# Replicape_A4A.net
KiCad netlist of a schematic drawn in EAGLE
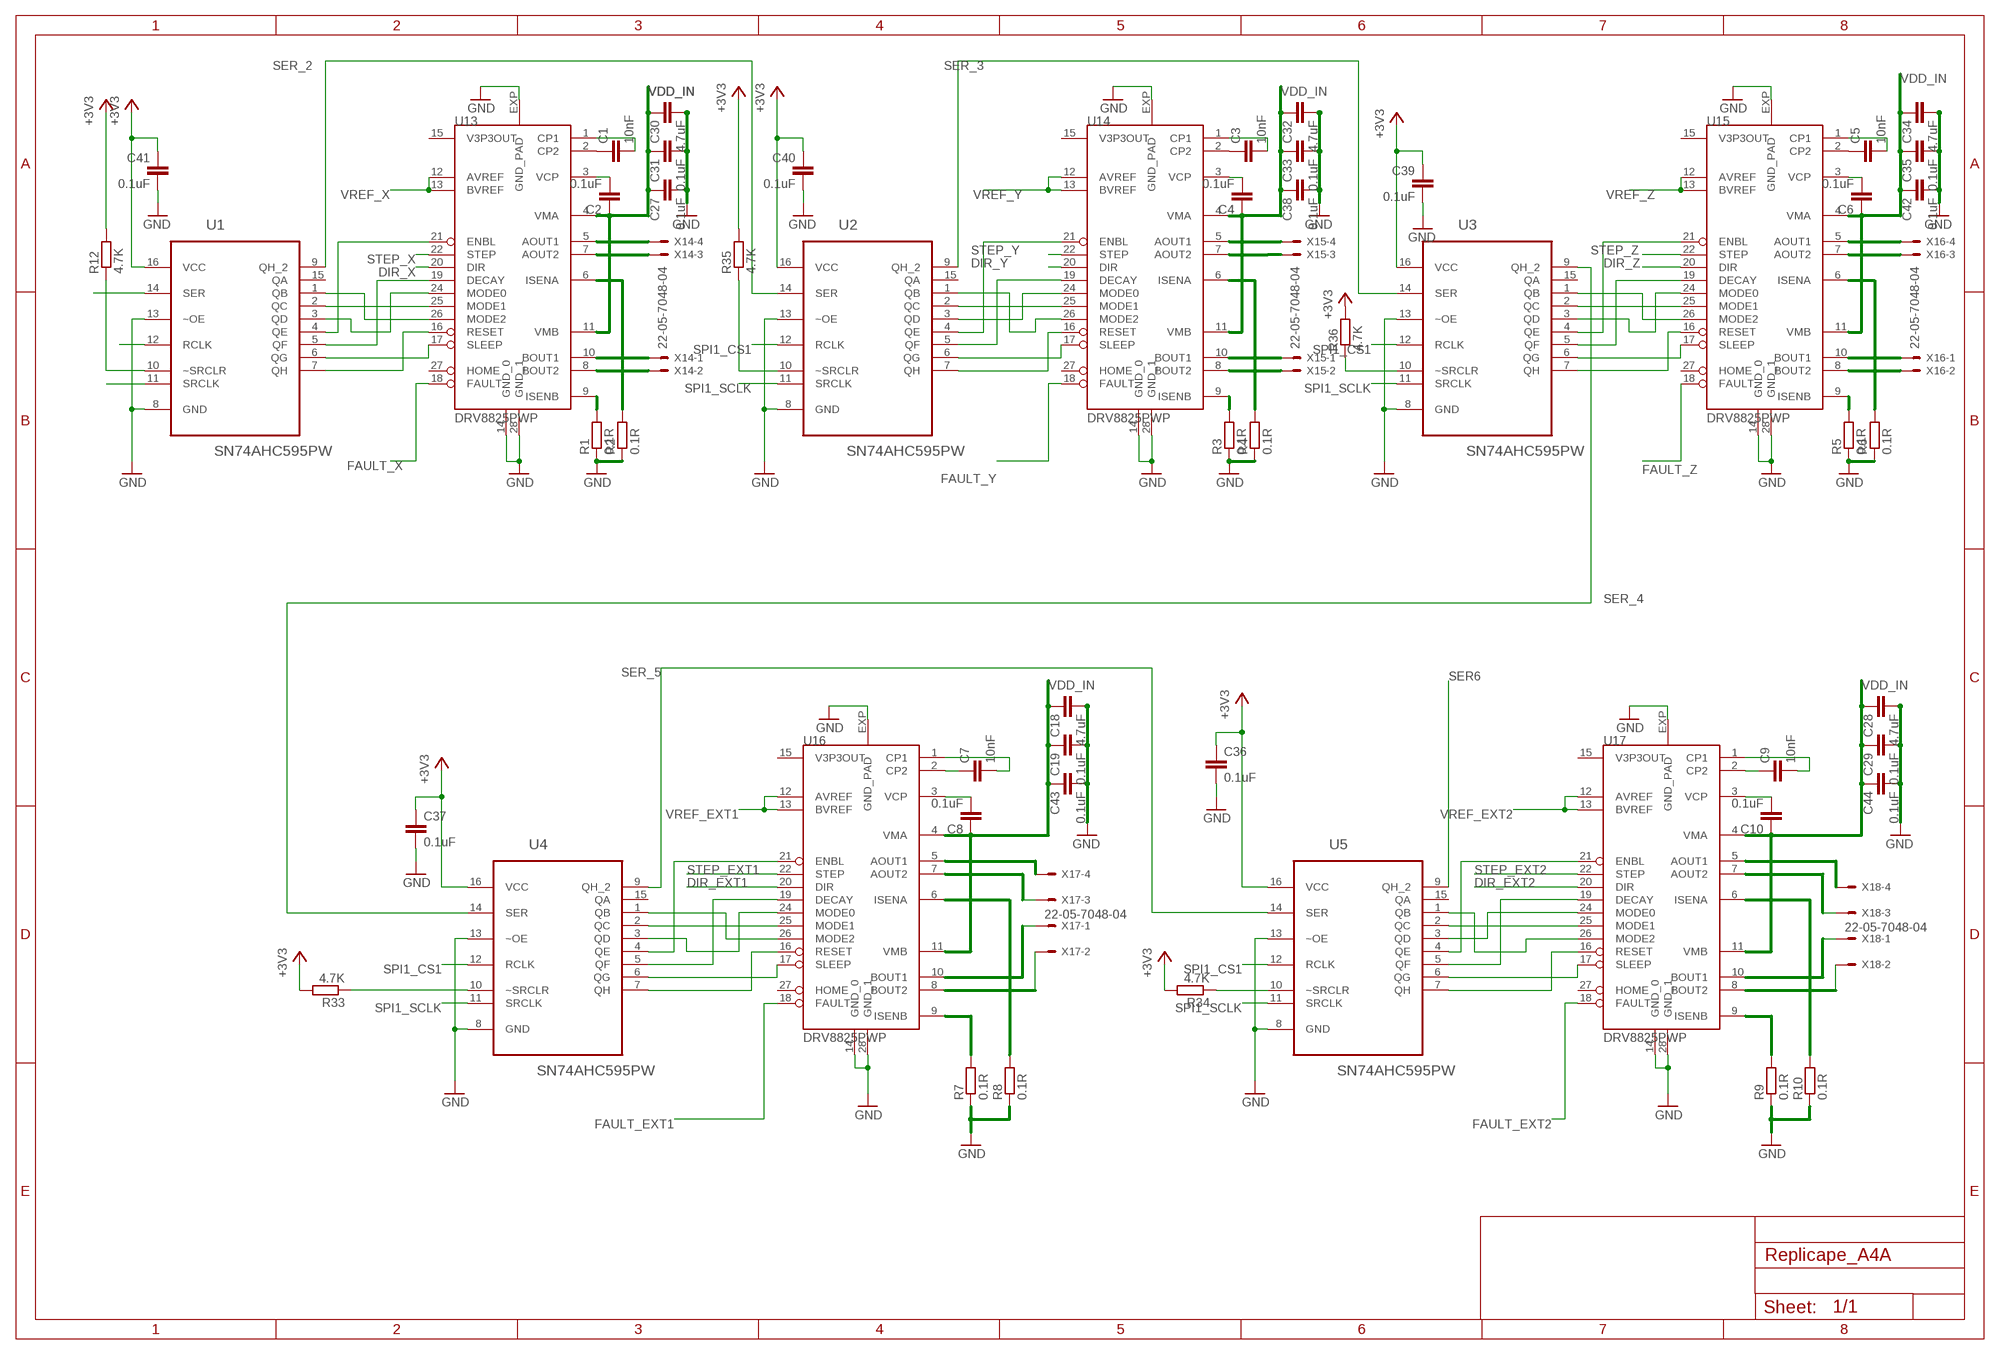
[diagram p0: schematic, sheet 1, part 1 of 3]
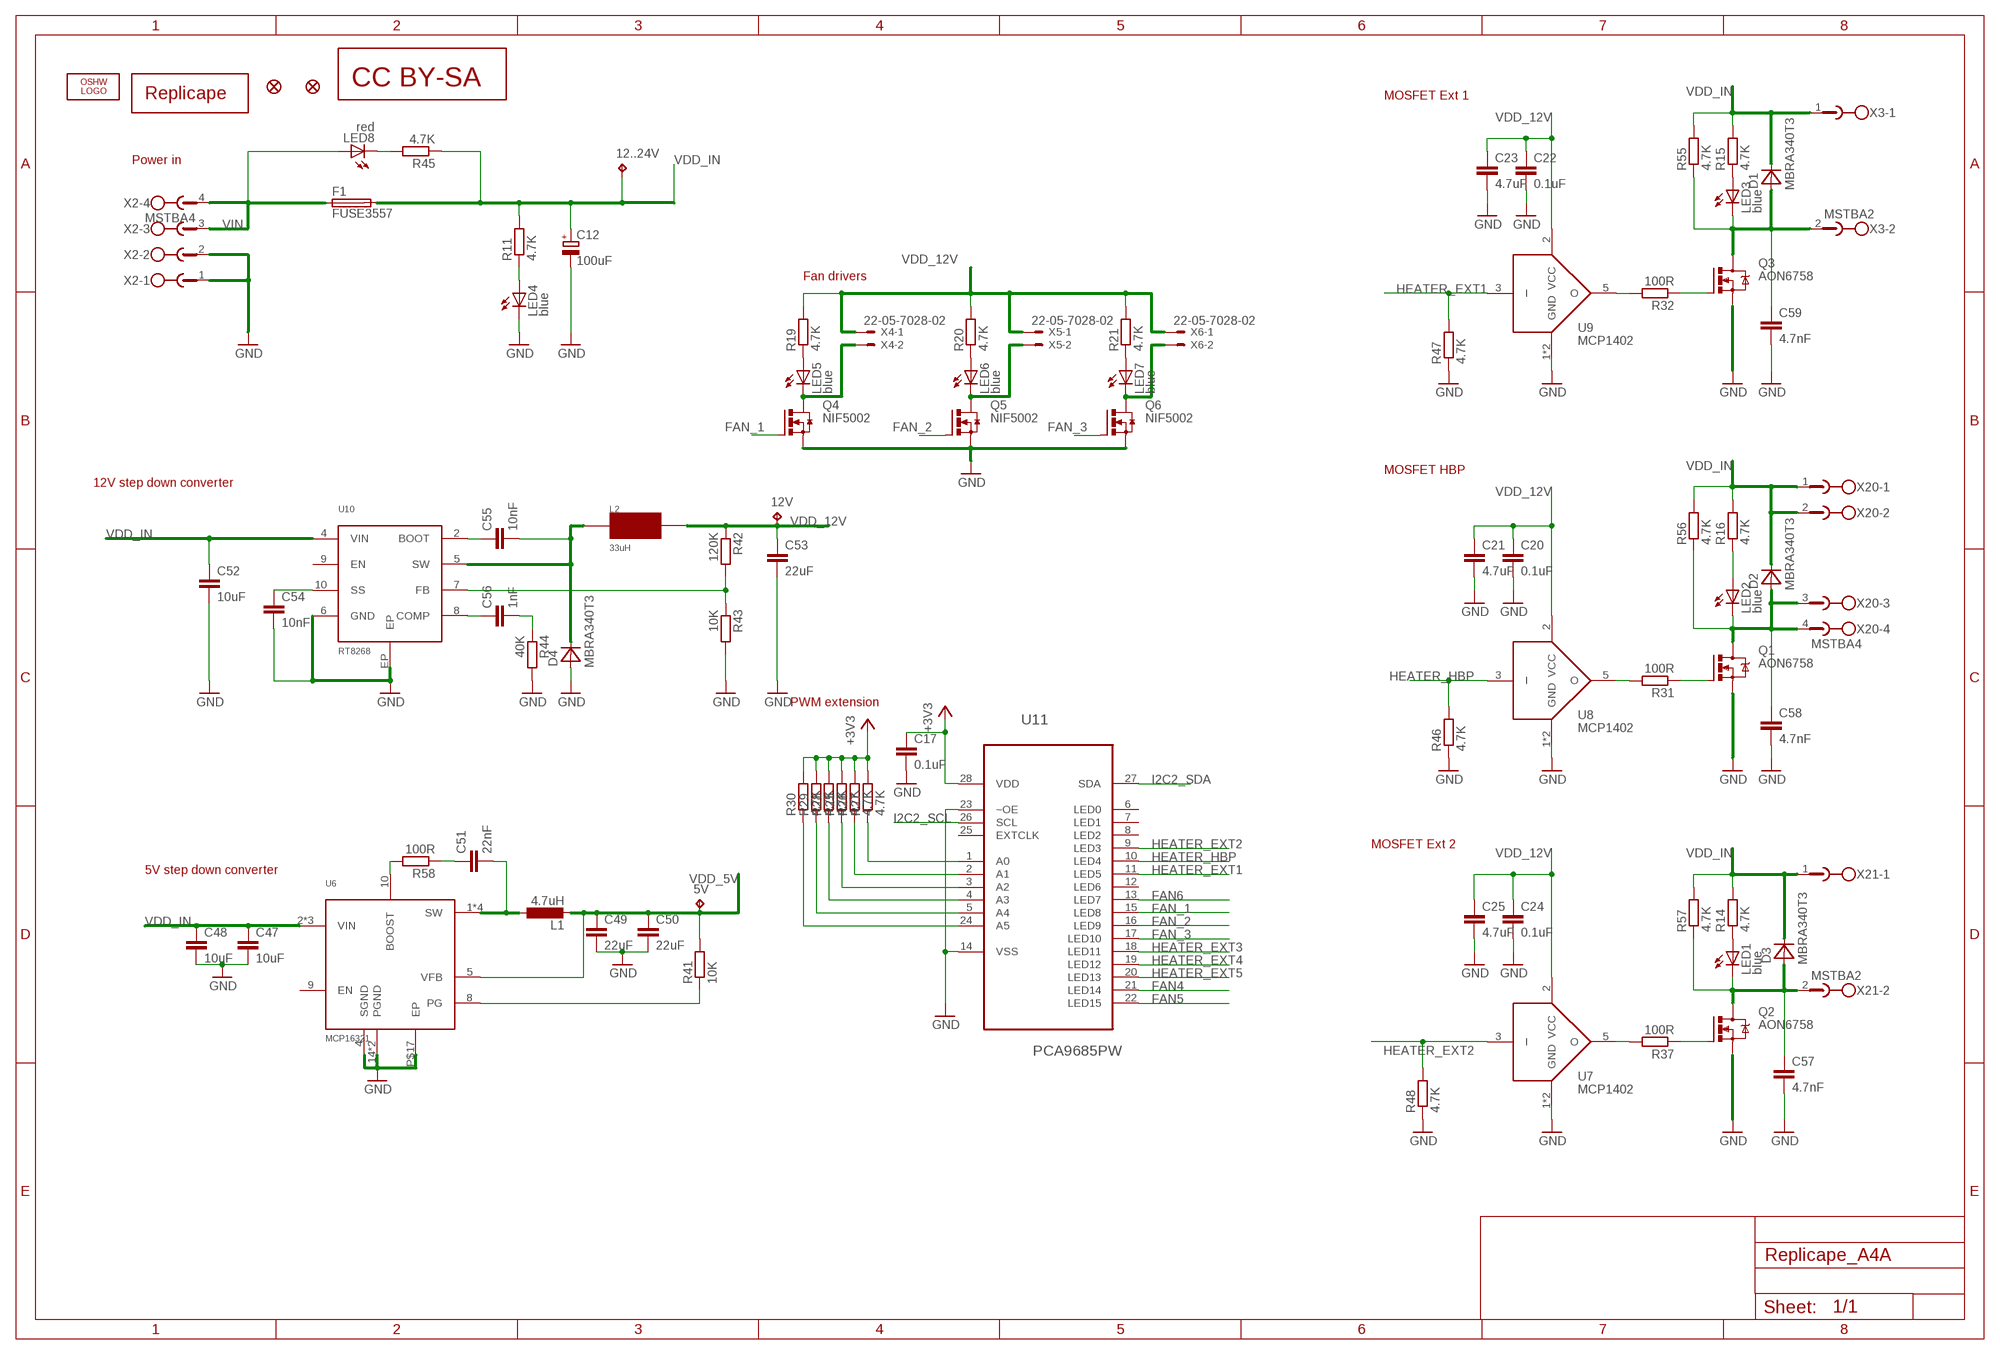
[diagram p1: schematic, sheet 1, part 2 of 3]
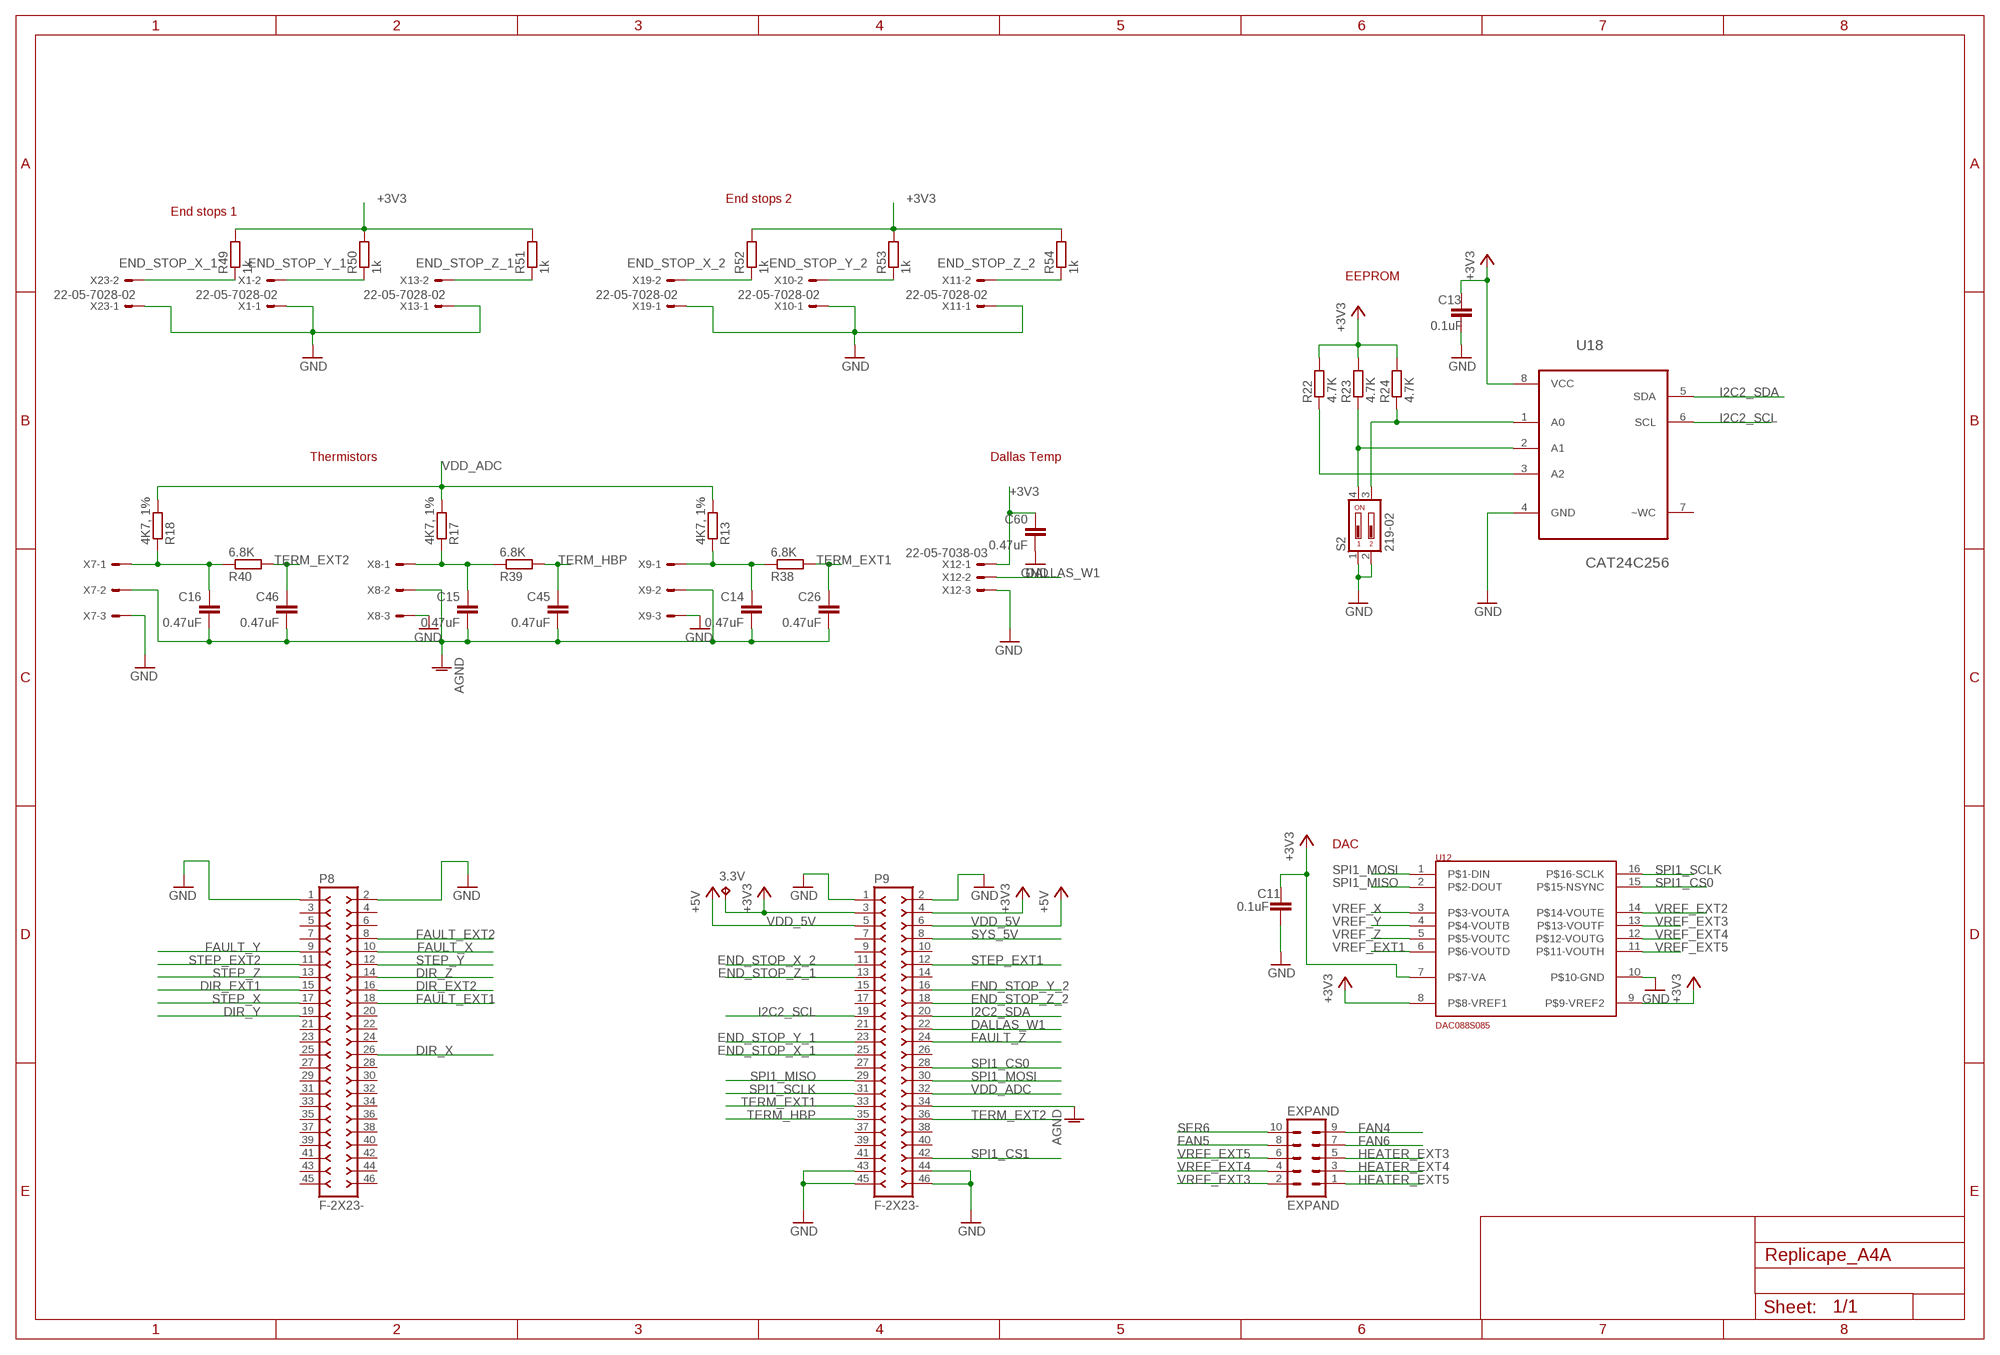
[diagram p2: schematic, sheet 1, part 3 of 3]

(export (version "E")
  (design (tool "Eeschema 10.0.6"))
  (components
    (comp (ref "3.3V")
      (value "TPB1,27")
      (footprint "eagle-import:B1,27")
      (libsource (lib "eagle-import") (part "TPB1,27"))
    )
    (comp (ref "5V")
      (value "TPB1,27")
      (footprint "eagle-import:B1,27")
      (libsource (lib "eagle-import") (part "TPB1,27"))
    )
    (comp (ref "12..24V")
      (value "TPB1,27")
      (footprint "eagle-import:B1,27")
      (libsource (lib "eagle-import") (part "TPB1,27"))
    )
    (comp (ref "12V")
      (value "TPB1,27")
      (footprint "eagle-import:B1,27")
      (libsource (lib "eagle-import") (part "TPB1,27"))
    )
    (comp (ref "C1")
      (value "10nF")
      (footprint "eagle-import:C0402")
      (libsource (lib "eagle-import") (part "C-EUC0402"))
    )
    (comp (ref "C2")
      (value "0.1uF")
      (footprint "eagle-import:C0402")
      (libsource (lib "eagle-import") (part "C-EUC0402"))
    )
    (comp (ref "C3")
      (value "10nF")
      (footprint "eagle-import:C0402")
      (libsource (lib "eagle-import") (part "C-EUC0402"))
    )
    (comp (ref "C4")
      (value "0.1uF")
      (footprint "eagle-import:C0402")
      (libsource (lib "eagle-import") (part "C-EUC0402"))
    )
    (comp (ref "C5")
      (value "10nF")
      (footprint "eagle-import:C0402")
      (libsource (lib "eagle-import") (part "C-EUC0402"))
    )
    (comp (ref "C6")
      (value "0.1uF")
      (footprint "eagle-import:C0402")
      (libsource (lib "eagle-import") (part "C-EUC0402"))
    )
    (comp (ref "C7")
      (value "10nF")
      (footprint "eagle-import:C0402")
      (libsource (lib "eagle-import") (part "C-EUC0402"))
    )
    (comp (ref "C8")
      (value "0.1uF")
      (footprint "eagle-import:C0402")
      (libsource (lib "eagle-import") (part "C-EUC0402"))
    )
    (comp (ref "C9")
      (value "10nF")
      (footprint "eagle-import:C0402")
      (libsource (lib "eagle-import") (part "C-EUC0402"))
    )
    (comp (ref "C10")
      (value "0.1uF")
      (footprint "eagle-import:C0402")
      (libsource (lib "eagle-import") (part "C-EUC0402"))
    )
    (comp (ref "C11")
      (value "0.1uF")
      (footprint "eagle-import:C0402")
      (libsource (lib "eagle-import") (part "C-EUC0402"))
    )
    (comp (ref "C12")
      (value "100uF")
      (footprint "eagle-import:140CLH-0810")
      (libsource (lib "eagle-import") (part "CPOL-EU140CLH-0810"))
    )
    (comp (ref "C13")
      (value "0.1uF")
      (footprint "eagle-import:C0402")
      (libsource (lib "eagle-import") (part "C-EUC0402"))
    )
    (comp (ref "C14")
      (value "0.47uF")
      (footprint "eagle-import:C0402")
      (libsource (lib "eagle-import") (part "C-EUC0402"))
    )
    (comp (ref "C15")
      (value "0.47uF")
      (footprint "eagle-import:C0402")
      (libsource (lib "eagle-import") (part "C-EUC0402"))
    )
    (comp (ref "C16")
      (value "0.47uF")
      (footprint "eagle-import:C0402")
      (libsource (lib "eagle-import") (part "C-EUC0402"))
    )
    (comp (ref "C17")
      (value "0.1uF")
      (footprint "eagle-import:C0402")
      (libsource (lib "eagle-import") (part "C-EUC0402"))
    )
    (comp (ref "C18")
      (value "4.7uF")
      (footprint "eagle-import:C0603")
      (libsource (lib "eagle-import") (part "C-EUC0603"))
    )
    (comp (ref "C19")
      (value "0.1uF")
      (footprint "eagle-import:C0402")
      (libsource (lib "eagle-import") (part "C-EUC0402"))
    )
    (comp (ref "C20")
      (value "0.1uF")
      (footprint "eagle-import:C0402")
      (libsource (lib "eagle-import") (part "C-EUC0402"))
    )
    (comp (ref "C21")
      (value "4.7uF")
      (footprint "eagle-import:C0402")
      (libsource (lib "eagle-import") (part "C-EUC0402"))
    )
    (comp (ref "C22")
      (value "0.1uF")
      (footprint "eagle-import:C0402")
      (libsource (lib "eagle-import") (part "C-EUC0402"))
    )
    (comp (ref "C23")
      (value "4.7uF")
      (footprint "eagle-import:C0402")
      (libsource (lib "eagle-import") (part "C-EUC0402"))
    )
    (comp (ref "C24")
      (value "0.1uF")
      (footprint "eagle-import:C0402")
      (libsource (lib "eagle-import") (part "C-EUC0402"))
    )
    (comp (ref "C25")
      (value "4.7uF")
      (footprint "eagle-import:C0402")
      (libsource (lib "eagle-import") (part "C-EUC0402"))
    )
    (comp (ref "C26")
      (value "0.47uF")
      (footprint "eagle-import:C0402")
      (libsource (lib "eagle-import") (part "C-EUC0402"))
    )
    (comp (ref "C27")
      (value "0.1uF")
      (footprint "eagle-import:C0402")
      (libsource (lib "eagle-import") (part "C-EUC0402"))
    )
    (comp (ref "C28")
      (value "4.7uF")
      (footprint "eagle-import:C0603")
      (libsource (lib "eagle-import") (part "C-EUC0603"))
    )
    (comp (ref "C29")
      (value "0.1uF")
      (footprint "eagle-import:C0402")
      (libsource (lib "eagle-import") (part "C-EUC0402"))
    )
    (comp (ref "C30")
      (value "4.7uF")
      (footprint "eagle-import:C0603")
      (libsource (lib "eagle-import") (part "C-EUC0603"))
    )
    (comp (ref "C31")
      (value "0.1uF")
      (footprint "eagle-import:C0402")
      (libsource (lib "eagle-import") (part "C-EUC0402"))
    )
    (comp (ref "C32")
      (value "4.7uF")
      (footprint "eagle-import:C0603")
      (libsource (lib "eagle-import") (part "C-EUC0603"))
    )
    (comp (ref "C33")
      (value "0.1uF")
      (footprint "eagle-import:C0402")
      (libsource (lib "eagle-import") (part "C-EUC0402"))
    )
    (comp (ref "C34")
      (value "4.7uF")
      (footprint "eagle-import:C0603")
      (libsource (lib "eagle-import") (part "C-EUC0603"))
    )
    (comp (ref "C35")
      (value "0.1uF")
      (footprint "eagle-import:C0402")
      (libsource (lib "eagle-import") (part "C-EUC0402"))
    )
    (comp (ref "C36")
      (value "0.1uF")
      (footprint "eagle-import:C0402")
      (libsource (lib "eagle-import") (part "C-EUC0402"))
    )
    (comp (ref "C37")
      (value "0.1uF")
      (footprint "eagle-import:C0402")
      (libsource (lib "eagle-import") (part "C-EUC0402"))
    )
    (comp (ref "C38")
      (value "0.1uF")
      (footprint "eagle-import:C0402")
      (libsource (lib "eagle-import") (part "C-EUC0402"))
    )
    (comp (ref "C39")
      (value "0.1uF")
      (footprint "eagle-import:C0402")
      (libsource (lib "eagle-import") (part "C-EUC0402"))
    )
    (comp (ref "C40")
      (value "0.1uF")
      (footprint "eagle-import:C0402")
      (libsource (lib "eagle-import") (part "C-EUC0402"))
    )
    (comp (ref "C41")
      (value "0.1uF")
      (footprint "eagle-import:C0402")
      (libsource (lib "eagle-import") (part "C-EUC0402"))
    )
    (comp (ref "C42")
      (value "0.1uF")
      (footprint "eagle-import:C0402")
      (libsource (lib "eagle-import") (part "C-EUC0402"))
    )
    (comp (ref "C43")
      (value "0.1uF")
      (footprint "eagle-import:C0402")
      (libsource (lib "eagle-import") (part "C-EUC0402"))
    )
    (comp (ref "C44")
      (value "0.1uF")
      (footprint "eagle-import:C0402")
      (libsource (lib "eagle-import") (part "C-EUC0402"))
    )
    (comp (ref "C45")
      (value "0.47uF")
      (footprint "eagle-import:C0402")
      (libsource (lib "eagle-import") (part "C-EUC0402"))
    )
    (comp (ref "C46")
      (value "0.47uF")
      (footprint "eagle-import:C0402")
      (libsource (lib "eagle-import") (part "C-EUC0402"))
    )
    (comp (ref "C47")
      (value "10uF")
      (footprint "eagle-import:C1206")
      (libsource (lib "eagle-import") (part "C-EUC1206"))
    )
    (comp (ref "C48")
      (value "10uF")
      (footprint "eagle-import:C1206")
      (libsource (lib "eagle-import") (part "C-EUC1206"))
    )
    (comp (ref "C49")
      (value "22uF")
      (footprint "eagle-import:C0805")
      (libsource (lib "eagle-import") (part "C-EUC0805"))
    )
    (comp (ref "C50")
      (value "22uF")
      (footprint "eagle-import:C0805")
      (libsource (lib "eagle-import") (part "C-EUC0805"))
    )
    (comp (ref "C51")
      (value "22nF")
      (footprint "eagle-import:C0402")
      (libsource (lib "eagle-import") (part "C-EUC0402"))
    )
    (comp (ref "C52")
      (value "10uF")
      (footprint "eagle-import:C1206")
      (libsource (lib "eagle-import") (part "C-EUC1206"))
    )
    (comp (ref "C53")
      (value "22uF")
      (footprint "eagle-import:C0805")
      (libsource (lib "eagle-import") (part "C-EUC0805"))
    )
    (comp (ref "C54")
      (value "10nF")
      (footprint "eagle-import:C0402")
      (libsource (lib "eagle-import") (part "C-EUC0402"))
    )
    (comp (ref "C55")
      (value "10nF")
      (footprint "eagle-import:C0402")
      (libsource (lib "eagle-import") (part "C-EUC0402"))
    )
    (comp (ref "C56")
      (value "1nF")
      (footprint "eagle-import:C0402")
      (libsource (lib "eagle-import") (part "C-EUC0402"))
    )
    (comp (ref "C57")
      (value "4.7nF")
      (footprint "eagle-import:C0402")
      (libsource (lib "eagle-import") (part "C-EUC0402"))
    )
    (comp (ref "C58")
      (value "4.7nF")
      (footprint "eagle-import:C0402")
      (libsource (lib "eagle-import") (part "C-EUC0402"))
    )
    (comp (ref "C59")
      (value "4.7nF")
      (footprint "eagle-import:C0402")
      (libsource (lib "eagle-import") (part "C-EUC0402"))
    )
    (comp (ref "C60")
      (value "0.47uF")
      (footprint "eagle-import:C0402")
      (libsource (lib "eagle-import") (part "C-EUC0402"))
    )
    (comp (ref "D1")
      (value "MBRA340T3")
      (footprint "eagle-import:SMA")
      (libsource (lib "eagle-import") (part "MBRA340T3"))
    )
    (comp (ref "D2")
      (value "MBRA340T3")
      (footprint "eagle-import:SMA")
      (libsource (lib "eagle-import") (part "MBRA340T3"))
    )
    (comp (ref "D3")
      (value "MBRA340T3")
      (footprint "eagle-import:SMA")
      (libsource (lib "eagle-import") (part "MBRA340T3"))
    )
    (comp (ref "D4")
      (value "MBRA340T3")
      (footprint "eagle-import:SMA")
      (libsource (lib "eagle-import") (part "MBRA340T3"))
    )
    (comp (ref "EXPAND")
      (value "EXPAND")
      (footprint "eagle-import:MA05-2")
      (libsource (lib "eagle-import") (part "MA05-2"))
    )
    (comp (ref "F1")
      (value "FUSE3557")
      (footprint "eagle-import:3557")
      (libsource (lib "eagle-import") (part "FUSE3557"))
    )
    (comp (ref "JP1")
      (value "FIDUCIAL1X2.5")
      (footprint "eagle-import:FIDUCIAL-1X2.5")
      (libsource (lib "eagle-import") (part "FIDUCIAL1X2.5"))
    )
    (comp (ref "JP2")
      (value "FIDUCIAL1X2.5")
      (footprint "eagle-import:FIDUCIAL-1X2.5")
      (libsource (lib "eagle-import") (part "FIDUCIAL1X2.5"))
    )
    (comp (ref "L1")
      (value "4.7uH")
      (footprint "eagle-import:VLC5020")
      (libsource (lib "eagle-import") (part "L-EUVLC"))
    )
    (comp (ref "L2")
      (value "33uH")
      (footprint "eagle-import:NR8040T330")
      (libsource (lib "eagle-import") (part "RT8040T330"))
    )
    (comp (ref "LED1")
      (value "blue")
      (footprint "eagle-import:CHIP-LED0603")
      (libsource (lib "eagle-import") (part "LEDCHIP-LED0603"))
    )
    (comp (ref "LED2")
      (value "blue")
      (footprint "eagle-import:CHIP-LED0603")
      (libsource (lib "eagle-import") (part "LEDCHIP-LED0603"))
    )
    (comp (ref "LED3")
      (value "blue")
      (footprint "eagle-import:CHIP-LED0603")
      (libsource (lib "eagle-import") (part "LEDCHIP-LED0603"))
    )
    (comp (ref "LED4")
      (value "blue")
      (footprint "eagle-import:CHIP-LED0603")
      (libsource (lib "eagle-import") (part "LEDCHIP-LED0603"))
    )
    (comp (ref "LED5")
      (value "blue")
      (footprint "eagle-import:CHIP-LED0603")
      (libsource (lib "eagle-import") (part "LEDCHIP-LED0603"))
    )
    (comp (ref "LED6")
      (value "blue")
      (footprint "eagle-import:CHIP-LED0603")
      (libsource (lib "eagle-import") (part "LEDCHIP-LED0603"))
    )
    (comp (ref "LED7")
      (value "blue")
      (footprint "eagle-import:CHIP-LED0603")
      (libsource (lib "eagle-import") (part "LEDCHIP-LED0603"))
    )
    (comp (ref "LED8")
      (value "red")
      (footprint "eagle-import:CHIP-LED0603")
      (libsource (lib "eagle-import") (part "LEDCHIP-LED0603"))
    )
    (comp (ref "LOGO1")
      (value "OSHW_LOGO_FILLX0200-NT")
      (footprint "eagle-import:OSHW_FILLX200_NOTEXT")
      (libsource (lib "eagle-import") (part "OSHW_LOGO_FILLX0200-NT"))
    )
    (comp (ref "P8")
      (value "F-2X23-")
      (footprint "eagle-import:DIL-100-2X23")
      (libsource (lib "eagle-import") (part "F-2X23-"))
    )
    (comp (ref "P9")
      (value "F-2X23-")
      (footprint "eagle-import:DIL-100-2X23")
      (libsource (lib "eagle-import") (part "F-2X23-"))
    )
    (comp (ref "Q1")
      (value "AON6758")
      (footprint "eagle-import:8-DFN-EP-(5X6)")
      (libsource (lib "eagle-import") (part "AON6758"))
    )
    (comp (ref "Q2")
      (value "AON6758")
      (footprint "eagle-import:8-DFN-EP-(5X6)")
      (libsource (lib "eagle-import") (part "AON6758"))
    )
    (comp (ref "Q3")
      (value "AON6758")
      (footprint "eagle-import:8-DFN-EP-(5X6)")
      (libsource (lib "eagle-import") (part "AON6758"))
    )
    (comp (ref "Q4")
      (value "NIF5002")
      (footprint "eagle-import:SOT223")
      (libsource (lib "eagle-import") (part "N-HEXFET-2D_?-SOT232"))
    )
    (comp (ref "Q5")
      (value "NIF5002")
      (footprint "eagle-import:SOT223")
      (libsource (lib "eagle-import") (part "N-HEXFET-2D_?-SOT232"))
    )
    (comp (ref "Q6")
      (value "NIF5002")
      (footprint "eagle-import:SOT223")
      (libsource (lib "eagle-import") (part "N-HEXFET-2D_?-SOT232"))
    )
    (comp (ref "R1")
      (value "0.1R")
      (footprint "eagle-import:R0805")
      (libsource (lib "eagle-import") (part "R-EU_R0805"))
    )
    (comp (ref "R2")
      (value "0.1R")
      (footprint "eagle-import:R0805")
      (libsource (lib "eagle-import") (part "R-EU_R0805"))
    )
    (comp (ref "R3")
      (value "0.1R")
      (footprint "eagle-import:R0805")
      (libsource (lib "eagle-import") (part "R-EU_R0805"))
    )
    (comp (ref "R4")
      (value "0.1R")
      (footprint "eagle-import:R0805")
      (libsource (lib "eagle-import") (part "R-EU_R0805"))
    )
    (comp (ref "R5")
      (value "0.1R")
      (footprint "eagle-import:R0805")
      (libsource (lib "eagle-import") (part "R-EU_R0805"))
    )
    (comp (ref "R6")
      (value "0.1R")
      (footprint "eagle-import:R0805")
      (libsource (lib "eagle-import") (part "R-EU_R0805"))
    )
    (comp (ref "R7")
      (value "0.1R")
      (footprint "eagle-import:R0805")
      (libsource (lib "eagle-import") (part "R-EU_R0805"))
    )
    (comp (ref "R8")
      (value "0.1R")
      (footprint "eagle-import:R0805")
      (libsource (lib "eagle-import") (part "R-EU_R0805"))
    )
    (comp (ref "R9")
      (value "0.1R")
      (footprint "eagle-import:R0805")
      (libsource (lib "eagle-import") (part "R-EU_R0805"))
    )
    (comp (ref "R10")
      (value "0.1R")
      (footprint "eagle-import:R0805")
      (libsource (lib "eagle-import") (part "R-EU_R0805"))
    )
    (comp (ref "R11")
      (value "4.7K")
      (footprint "eagle-import:R0402")
      (libsource (lib "eagle-import") (part "R-EU_R0402"))
    )
    (comp (ref "R12")
      (value "4.7K")
      (footprint "eagle-import:R0402")
      (libsource (lib "eagle-import") (part "R-EU_R0402"))
    )
    (comp (ref "R13")
      (value "4K7, 1%")
      (footprint "eagle-import:R0402")
      (libsource (lib "eagle-import") (part "R-EU_R0402"))
    )
    (comp (ref "R14")
      (value "4.7K")
      (footprint "eagle-import:R0402")
      (libsource (lib "eagle-import") (part "R-EU_R0402"))
    )
    (comp (ref "R15")
      (value "4.7K")
      (footprint "eagle-import:R0402")
      (libsource (lib "eagle-import") (part "R-EU_R0402"))
    )
    (comp (ref "R16")
      (value "4.7K")
      (footprint "eagle-import:R0402")
      (libsource (lib "eagle-import") (part "R-EU_R0402"))
    )
    (comp (ref "R17")
      (value "4K7, 1%")
      (footprint "eagle-import:R0402")
      (libsource (lib "eagle-import") (part "R-EU_R0402"))
    )
    (comp (ref "R18")
      (value "4K7, 1%")
      (footprint "eagle-import:R0402")
      (libsource (lib "eagle-import") (part "R-EU_R0402"))
    )
    (comp (ref "R19")
      (value "4.7K")
      (footprint "eagle-import:R0402")
      (libsource (lib "eagle-import") (part "R-EU_R0402"))
    )
    (comp (ref "R20")
      (value "4.7K")
      (footprint "eagle-import:R0402")
      (libsource (lib "eagle-import") (part "R-EU_R0402"))
    )
    (comp (ref "R21")
      (value "4.7K")
      (footprint "eagle-import:R0402")
      (libsource (lib "eagle-import") (part "R-EU_R0402"))
    )
    (comp (ref "R22")
      (value "4.7K")
      (footprint "eagle-import:R0402")
      (libsource (lib "eagle-import") (part "R-EU_R0402"))
    )
    (comp (ref "R23")
      (value "4.7K")
      (footprint "eagle-import:R0402")
      (libsource (lib "eagle-import") (part "R-EU_R0402"))
    )
    (comp (ref "R24")
      (value "4.7K")
      (footprint "eagle-import:R0402")
      (libsource (lib "eagle-import") (part "R-EU_R0402"))
    )
    (comp (ref "R25")
      (value "4.7K")
      (footprint "eagle-import:R0402")
      (libsource (lib "eagle-import") (part "R-EU_R0402"))
    )
    (comp (ref "R26")
      (value "4.7K")
      (footprint "eagle-import:R0402")
      (libsource (lib "eagle-import") (part "R-EU_R0402"))
    )
    (comp (ref "R27")
      (value "4.7K")
      (footprint "eagle-import:R0402")
      (libsource (lib "eagle-import") (part "R-EU_R0402"))
    )
    (comp (ref "R28")
      (value "4.7K")
      (footprint "eagle-import:R0402")
      (libsource (lib "eagle-import") (part "R-EU_R0402"))
    )
    (comp (ref "R29")
      (value "4.7K")
      (footprint "eagle-import:R0402")
      (libsource (lib "eagle-import") (part "R-EU_R0402"))
    )
    (comp (ref "R30")
      (value "4.7K")
      (footprint "eagle-import:R0402")
      (libsource (lib "eagle-import") (part "R-EU_R0402"))
    )
    (comp (ref "R31")
      (value "100R")
      (footprint "eagle-import:R0402")
      (libsource (lib "eagle-import") (part "R-EU_R0402"))
    )
    (comp (ref "R32")
      (value "100R")
      (footprint "eagle-import:R0402")
      (libsource (lib "eagle-import") (part "R-EU_R0402"))
    )
    (comp (ref "R33")
      (value "4.7K")
      (footprint "eagle-import:R0402")
      (libsource (lib "eagle-import") (part "R-EU_R0402"))
    )
    (comp (ref "R34")
      (value "4.7K")
      (footprint "eagle-import:R0402")
      (libsource (lib "eagle-import") (part "R-EU_R0402"))
    )
    (comp (ref "R35")
      (value "4.7K")
      (footprint "eagle-import:R0402")
      (libsource (lib "eagle-import") (part "R-EU_R0402"))
    )
    (comp (ref "R36")
      (value "4.7K")
      (footprint "eagle-import:R0402")
      (libsource (lib "eagle-import") (part "R-EU_R0402"))
    )
    (comp (ref "R37")
      (value "100R")
      (footprint "eagle-import:R0402")
      (libsource (lib "eagle-import") (part "R-EU_R0402"))
    )
    (comp (ref "R38")
      (value "6.8K")
      (footprint "eagle-import:R0402")
      (libsource (lib "eagle-import") (part "R-EU_R0402"))
    )
    (comp (ref "R39")
      (value "6.8K")
      (footprint "eagle-import:R0402")
      (libsource (lib "eagle-import") (part "R-EU_R0402"))
    )
    (comp (ref "R40")
      (value "6.8K")
      (footprint "eagle-import:R0402")
      (libsource (lib "eagle-import") (part "R-EU_R0402"))
    )
    (comp (ref "R41")
      (value "10K")
      (footprint "eagle-import:R0402")
      (libsource (lib "eagle-import") (part "R-EU_R0402"))
    )
    (comp (ref "R42")
      (value "120K")
      (footprint "eagle-import:R0402")
      (libsource (lib "eagle-import") (part "R-EU_R0402"))
    )
    (comp (ref "R43")
      (value "10K")
      (footprint "eagle-import:R0402")
      (libsource (lib "eagle-import") (part "R-EU_R0402"))
    )
    (comp (ref "R44")
      (value "40K")
      (footprint "eagle-import:R0402")
      (libsource (lib "eagle-import") (part "R-EU_R0402"))
    )
    (comp (ref "R45")
      (value "4.7K")
      (footprint "eagle-import:R0402")
      (libsource (lib "eagle-import") (part "R-EU_R0402"))
    )
    (comp (ref "R46")
      (value "4.7K")
      (footprint "eagle-import:R0402")
      (libsource (lib "eagle-import") (part "R-EU_R0402"))
    )
    (comp (ref "R47")
      (value "4.7K")
      (footprint "eagle-import:R0402")
      (libsource (lib "eagle-import") (part "R-EU_R0402"))
    )
    (comp (ref "R48")
      (value "4.7K")
      (footprint "eagle-import:R0402")
      (libsource (lib "eagle-import") (part "R-EU_R0402"))
    )
    (comp (ref "R49")
      (value "1k")
      (footprint "eagle-import:R0402")
      (libsource (lib "eagle-import") (part "R-EUR0402"))
    )
    (comp (ref "R50")
      (value "1k")
      (footprint "eagle-import:R0402")
      (libsource (lib "eagle-import") (part "R-EUR0402"))
    )
    (comp (ref "R51")
      (value "1k")
      (footprint "eagle-import:R0402")
      (libsource (lib "eagle-import") (part "R-EUR0402"))
    )
    (comp (ref "R52")
      (value "1k")
      (footprint "eagle-import:R0402")
      (libsource (lib "eagle-import") (part "R-EUR0402"))
    )
    (comp (ref "R53")
      (value "1k")
      (footprint "eagle-import:R0402")
      (libsource (lib "eagle-import") (part "R-EUR0402"))
    )
    (comp (ref "R54")
      (value "1k")
      (footprint "eagle-import:R0402")
      (libsource (lib "eagle-import") (part "R-EUR0402"))
    )
    (comp (ref "R55")
      (value "4.7K")
      (footprint "eagle-import:R0402")
      (libsource (lib "eagle-import") (part "R-EU_R0402"))
    )
    (comp (ref "R56")
      (value "4.7K")
      (footprint "eagle-import:R0402")
      (libsource (lib "eagle-import") (part "R-EU_R0402"))
    )
    (comp (ref "R57")
      (value "4.7K")
      (footprint "eagle-import:R0402")
      (libsource (lib "eagle-import") (part "R-EU_R0402"))
    )
    (comp (ref "R58")
      (value "100R")
      (footprint "eagle-import:R0402")
      (libsource (lib "eagle-import") (part "R-EU_R0402"))
    )
    (comp (ref "S2")
      (value "219-02")
      (footprint "eagle-import:CTS-219-02")
      (libsource (lib "eagle-import") (part "219-02"))
    )
    (comp (ref "U$2")
      (value "REPLICAPE-LOGO")
      (footprint "eagle-import:REPLICAPE-LOGO")
      (libsource (lib "eagle-import") (part "REPLICAPE-LOGO"))
    )
    (comp (ref "U$3")
      (value "CC-BY-SA")
      (footprint "eagle-import:CC-BY-SA")
      (libsource (lib "eagle-import") (part "CC-BY-SA"))
    )
    (comp (ref "U1")
      (value "SN74AHC595PW")
      (footprint "eagle-import:SOP65P640X120-16N")
      (libsource (lib "eagle-import") (part "SN74AHC595PW"))
    )
    (comp (ref "U2")
      (value "SN74AHC595PW")
      (footprint "eagle-import:SOP65P640X120-16N")
      (libsource (lib "eagle-import") (part "SN74AHC595PW"))
    )
    (comp (ref "U3")
      (value "SN74AHC595PW")
      (footprint "eagle-import:SOP65P640X120-16N")
      (libsource (lib "eagle-import") (part "SN74AHC595PW"))
    )
    (comp (ref "U4")
      (value "SN74AHC595PW")
      (footprint "eagle-import:SOP65P640X120-16N")
      (libsource (lib "eagle-import") (part "SN74AHC595PW"))
    )
    (comp (ref "U5")
      (value "SN74AHC595PW")
      (footprint "eagle-import:SOP65P640X120-16N")
      (libsource (lib "eagle-import") (part "SN74AHC595PW"))
    )
    (comp (ref "U6")
      (value "MCP16321")
      (footprint "eagle-import:QFN-16")
      (libsource (lib "eagle-import") (part "MCP16321"))
    )
    (comp (ref "U7")
      (value "MCP1402")
      (footprint "eagle-import:SOT23-5L")
      (libsource (lib "eagle-import") (part "MCP1402"))
    )
    (comp (ref "U8")
      (value "MCP1402")
      (footprint "eagle-import:SOT23-5L")
      (libsource (lib "eagle-import") (part "MCP1402"))
    )
    (comp (ref "U9")
      (value "MCP1402")
      (footprint "eagle-import:SOT23-5L")
      (libsource (lib "eagle-import") (part "MCP1402"))
    )
    (comp (ref "U10")
      (value "RT8268")
      (footprint "eagle-import:MSOP10")
      (libsource (lib "eagle-import") (part "RT8268"))
    )
    (comp (ref "U11")
      (value "PCA9685PW")
      (footprint "eagle-import:SOP65P640X110-28N")
      (libsource (lib "eagle-import") (part "PCA9685PW"))
    )
    (comp (ref "U12")
      (value "DAC088S085")
      (footprint "eagle-import:TSSOP-16")
      (libsource (lib "eagle-import") (part "DAC088S085"))
    )
    (comp (ref "U13")
      (value "DRV8825PWP")
      (footprint "eagle-import:TSSOP-28")
      (libsource (lib "eagle-import") (part "DRV8825PWP"))
    )
    (comp (ref "U14")
      (value "DRV8825PWP")
      (footprint "eagle-import:TSSOP-28")
      (libsource (lib "eagle-import") (part "DRV8825PWP"))
    )
    (comp (ref "U15")
      (value "DRV8825PWP")
      (footprint "eagle-import:TSSOP-28")
      (libsource (lib "eagle-import") (part "DRV8825PWP"))
    )
    (comp (ref "U16")
      (value "DRV8825PWP")
      (footprint "eagle-import:TSSOP-28")
      (libsource (lib "eagle-import") (part "DRV8825PWP"))
    )
    (comp (ref "U17")
      (value "DRV8825PWP")
      (footprint "eagle-import:TSSOP-28")
      (libsource (lib "eagle-import") (part "DRV8825PWP"))
    )
    (comp (ref "U18")
      (value "CAT24C256")
      (footprint "eagle-import:SOIC127P600X175-8N")
      (libsource (lib "eagle-import") (part "CAT24C256"))
    )
    (comp (ref "X1")
      (value "22-05-7028-02")
      (footprint "eagle-import:7395-02")
      (libsource (lib "eagle-import") (part "22-?-0205-7028"))
    )
    (comp (ref "X2")
      (value "MSTBA4")
      (footprint "eagle-import:MSTBA4")
      (libsource (lib "eagle-import") (part "MSTBA4"))
    )
    (comp (ref "X3")
      (value "MSTBA2")
      (footprint "eagle-import:MSTBA2")
      (libsource (lib "eagle-import") (part "MSTBA2"))
    )
    (comp (ref "X4")
      (value "22-05-7028-02")
      (footprint "eagle-import:7395-02")
      (libsource (lib "eagle-import") (part "22-?-0205-7028"))
    )
    (comp (ref "X5")
      (value "22-05-7028-02")
      (footprint "eagle-import:7395-02")
      (libsource (lib "eagle-import") (part "22-?-0205-7028"))
    )
    (comp (ref "X6")
      (value "22-05-7028-02")
      (footprint "eagle-import:7395-02")
      (libsource (lib "eagle-import") (part "22-?-0205-7028"))
    )
    (comp (ref "X7")
      (value "22-05-7038-03")
      (footprint "eagle-import:7395-03")
      (libsource (lib "eagle-import") (part "22-?-0305-7038"))
    )
    (comp (ref "X8")
      (value "22-05-7038-03")
      (footprint "eagle-import:7395-03")
      (libsource (lib "eagle-import") (part "22-?-0305-7038"))
    )
    (comp (ref "X9")
      (value "22-05-7038-03")
      (footprint "eagle-import:7395-03")
      (libsource (lib "eagle-import") (part "22-?-0305-7038"))
    )
    (comp (ref "X10")
      (value "22-05-7028-02")
      (footprint "eagle-import:7395-02")
      (libsource (lib "eagle-import") (part "22-?-0205-7028"))
    )
    (comp (ref "X11")
      (value "22-05-7028-02")
      (footprint "eagle-import:7395-02")
      (libsource (lib "eagle-import") (part "22-?-0205-7028"))
    )
    (comp (ref "X12")
      (value "22-05-7038-03")
      (footprint "eagle-import:7395-03")
      (libsource (lib "eagle-import") (part "22-?-0305-7038"))
    )
    (comp (ref "X13")
      (value "22-05-7028-02")
      (footprint "eagle-import:7395-02")
      (libsource (lib "eagle-import") (part "22-?-0205-7028"))
    )
    (comp (ref "X14")
      (value "22-05-7048-04")
      (footprint "eagle-import:7395-04")
      (libsource (lib "eagle-import") (part "22-?-0405-7048"))
    )
    (comp (ref "X15")
      (value "22-05-7048-04")
      (footprint "eagle-import:7395-04")
      (libsource (lib "eagle-import") (part "22-?-0405-7048"))
    )
    (comp (ref "X16")
      (value "22-05-7048-04")
      (footprint "eagle-import:7395-04")
      (libsource (lib "eagle-import") (part "22-?-0405-7048"))
    )
    (comp (ref "X17")
      (value "22-05-7048-04")
      (footprint "eagle-import:7395-04")
      (libsource (lib "eagle-import") (part "22-?-0405-7048"))
    )
    (comp (ref "X18")
      (value "22-05-7048-04")
      (footprint "eagle-import:7395-04")
      (libsource (lib "eagle-import") (part "22-?-0405-7048"))
    )
    (comp (ref "X19")
      (value "22-05-7028-02")
      (footprint "eagle-import:7395-02")
      (libsource (lib "eagle-import") (part "22-?-0205-7028"))
    )
    (comp (ref "X20")
      (value "MSTBA4")
      (footprint "eagle-import:MSTBA4")
      (libsource (lib "eagle-import") (part "MSTBA4"))
    )
    (comp (ref "X21")
      (value "MSTBA2")
      (footprint "eagle-import:MSTBA2")
      (libsource (lib "eagle-import") (part "MSTBA2"))
    )
    (comp (ref "X23")
      (value "22-05-7028-02")
      (footprint "eagle-import:7395-02")
      (libsource (lib "eagle-import") (part "22-?-0205-7028"))
    )
  )
  (nets
    (net (code "1") (name "+3V3") (class "Default")
      (node (ref "3.3V") (pin "TP") (pinfunction "TP_TP") (pintype "input"))
      (node (ref "C11") (pin "1") (pinfunction "1_1") (pintype "passive"))
      (node (ref "C13") (pin "1") (pinfunction "1_1") (pintype "passive"))
      (node (ref "C17") (pin "1") (pinfunction "1_1") (pintype "passive"))
      (node (ref "C36") (pin "1") (pinfunction "1_1") (pintype "passive"))
      (node (ref "C37") (pin "1") (pinfunction "1_1") (pintype "passive"))
      (node (ref "C39") (pin "1") (pinfunction "1_1") (pintype "passive"))
      (node (ref "C40") (pin "1") (pinfunction "1_1") (pintype "passive"))
      (node (ref "C41") (pin "1") (pinfunction "1_1") (pintype "passive"))
      (node (ref "C60") (pin "1") (pinfunction "1_1") (pintype "passive"))
      (node (ref "P9") (pin "3") (pinfunction "3_3") (pintype "passive"))
      (node (ref "P9") (pin "4") (pinfunction "4_4") (pintype "passive"))
      (node (ref "R12") (pin "2") (pinfunction "2_2") (pintype "passive"))
      (node (ref "R22") (pin "2") (pinfunction "2_2") (pintype "passive"))
      (node (ref "R23") (pin "2") (pinfunction "2_2") (pintype "passive"))
      (node (ref "R24") (pin "2") (pinfunction "2_2") (pintype "passive"))
      (node (ref "R25") (pin "2") (pinfunction "2_2") (pintype "passive"))
      (node (ref "R26") (pin "2") (pinfunction "2_2") (pintype "passive"))
      (node (ref "R27") (pin "2") (pinfunction "2_2") (pintype "passive"))
      (node (ref "R28") (pin "2") (pinfunction "2_2") (pintype "passive"))
      (node (ref "R29") (pin "2") (pinfunction "2_2") (pintype "passive"))
      (node (ref "R30") (pin "2") (pinfunction "2_2") (pintype "passive"))
      (node (ref "R33") (pin "2") (pinfunction "2_2") (pintype "passive"))
      (node (ref "R34") (pin "2") (pinfunction "2_2") (pintype "passive"))
      (node (ref "R35") (pin "2") (pinfunction "2_2") (pintype "passive"))
      (node (ref "R36") (pin "2") (pinfunction "2_2") (pintype "passive"))
      (node (ref "R49") (pin "2") (pinfunction "2_2") (pintype "passive"))
      (node (ref "R50") (pin "2") (pinfunction "2_2") (pintype "passive"))
      (node (ref "R51") (pin "2") (pinfunction "2_2") (pintype "passive"))
      (node (ref "R52") (pin "2") (pinfunction "2_2") (pintype "passive"))
      (node (ref "R53") (pin "2") (pinfunction "2_2") (pintype "passive"))
      (node (ref "R54") (pin "2") (pinfunction "2_2") (pintype "passive"))
      (node (ref "U1") (pin "16") (pinfunction "VCC_16") (pintype "power_in"))
      (node (ref "U11") (pin "28") (pinfunction "VDD_28") (pintype "power_in"))
      (node (ref "U12") (pin "7") (pinfunction "P$7-VA_7") (pintype "bidirectional"))
      (node (ref "U12") (pin "8") (pinfunction "P$8-VREF1_8") (pintype "bidirectional"))
      (node (ref "U12") (pin "9") (pinfunction "P$9-VREF2_9") (pintype "bidirectional"))
      (node (ref "U18") (pin "8") (pinfunction "VCC_8") (pintype "power_in"))
      (node (ref "U2") (pin "16") (pinfunction "VCC_16") (pintype "power_in"))
      (node (ref "U3") (pin "16") (pinfunction "VCC_16") (pintype "power_in"))
      (node (ref "U4") (pin "16") (pinfunction "VCC_16") (pintype "power_in"))
      (node (ref "U5") (pin "16") (pinfunction "VCC_16") (pintype "power_in"))
      (node (ref "X12") (pin "1") (pinfunction "S_1") (pintype "passive"))
    )
    (net (code "2") (name "+5V") (class "Default")
      (node (ref "5V") (pin "TP") (pinfunction "TP_TP") (pintype "input"))
      (node (ref "C49") (pin "1") (pinfunction "1_1") (pintype "passive"))
      (node (ref "C50") (pin "1") (pinfunction "1_1") (pintype "passive"))
      (node (ref "L1") (pin "2") (pinfunction "2_2") (pintype "passive"))
      (node (ref "P9") (pin "5") (pinfunction "5_5") (pintype "passive"))
      (node (ref "P9") (pin "6") (pinfunction "6_6") (pintype "passive"))
      (node (ref "R41") (pin "2") (pinfunction "2_2") (pintype "passive"))
      (node (ref "U6") (pin "5") (pinfunction "VFB_5") (pintype "input"))
    )
    (net (code "3") (name "/DALLAS_W1") (class "Default")
      (node (ref "P9") (pin "22") (pinfunction "22_22") (pintype "passive"))
      (node (ref "X12") (pin "2") (pinfunction "S_2") (pintype "passive"))
    )
    (net (code "4") (name "/DIR_EXT1") (class "Default")
      (node (ref "P8") (pin "15") (pinfunction "15_15") (pintype "passive"))
      (node (ref "U16") (pin "20") (pinfunction "DIR_20") (pintype "input"))
    )
    (net (code "5") (name "/DIR_EXT2") (class "Default")
      (node (ref "P8") (pin "16") (pinfunction "16_16") (pintype "passive"))
      (node (ref "U17") (pin "20") (pinfunction "DIR_20") (pintype "input"))
    )
    (net (code "6") (name "/DIR_X") (class "Default")
      (node (ref "P8") (pin "26") (pinfunction "26_26") (pintype "passive"))
      (node (ref "U13") (pin "20") (pinfunction "DIR_20") (pintype "input"))
    )
    (net (code "7") (name "/DIR_Y") (class "Default")
      (node (ref "P8") (pin "19") (pinfunction "19_19") (pintype "passive"))
      (node (ref "U14") (pin "20") (pinfunction "DIR_20") (pintype "input"))
    )
    (net (code "8") (name "/DIR_Z") (class "Default")
      (node (ref "P8") (pin "14") (pinfunction "14_14") (pintype "passive"))
      (node (ref "U15") (pin "20") (pinfunction "DIR_20") (pintype "input"))
    )
    (net (code "9") (name "/END_STOP_X_1") (class "Default")
      (node (ref "P9") (pin "25") (pinfunction "25_25") (pintype "passive"))
      (node (ref "R49") (pin "1") (pinfunction "1_1") (pintype "passive"))
      (node (ref "X23") (pin "2") (pinfunction "S_2") (pintype "passive"))
    )
    (net (code "10") (name "/END_STOP_X_2") (class "Default")
      (node (ref "P9") (pin "11") (pinfunction "11_11") (pintype "passive"))
      (node (ref "R52") (pin "1") (pinfunction "1_1") (pintype "passive"))
      (node (ref "X19") (pin "2") (pinfunction "S_2") (pintype "passive"))
    )
    (net (code "11") (name "/END_STOP_Y_1") (class "Default")
      (node (ref "P9") (pin "23") (pinfunction "23_23") (pintype "passive"))
      (node (ref "R50") (pin "1") (pinfunction "1_1") (pintype "passive"))
      (node (ref "X1") (pin "2") (pinfunction "S_2") (pintype "passive"))
    )
    (net (code "12") (name "/END_STOP_Y_2") (class "Default")
      (node (ref "P9") (pin "16") (pinfunction "16_16") (pintype "passive"))
      (node (ref "R53") (pin "1") (pinfunction "1_1") (pintype "passive"))
      (node (ref "X10") (pin "2") (pinfunction "S_2") (pintype "passive"))
    )
    (net (code "13") (name "/END_STOP_Z_1") (class "Default")
      (node (ref "P9") (pin "13") (pinfunction "13_13") (pintype "passive"))
      (node (ref "R51") (pin "1") (pinfunction "1_1") (pintype "passive"))
      (node (ref "X13") (pin "2") (pinfunction "S_2") (pintype "passive"))
    )
    (net (code "14") (name "/END_STOP_Z_2") (class "Default")
      (node (ref "P9") (pin "18") (pinfunction "18_18") (pintype "passive"))
      (node (ref "R54") (pin "1") (pinfunction "1_1") (pintype "passive"))
      (node (ref "X11") (pin "2") (pinfunction "S_2") (pintype "passive"))
    )
    (net (code "15") (name "/FAN4") (class "Default")
      (node (ref "EXPAND") (pin "9") (pinfunction "9_9") (pintype "passive"))
      (node (ref "U11") (pin "21") (pinfunction "LED14_21") (pintype "output"))
    )
    (net (code "16") (name "/FAN5") (class "Default")
      (node (ref "EXPAND") (pin "8") (pinfunction "8_8") (pintype "passive"))
      (node (ref "U11") (pin "22") (pinfunction "LED15_22") (pintype "output"))
    )
    (net (code "17") (name "/FAN6") (class "Default")
      (node (ref "EXPAND") (pin "7") (pinfunction "7_7") (pintype "passive"))
      (node (ref "U11") (pin "13") (pinfunction "LED7_13") (pintype "output"))
    )
    (net (code "18") (name "/FAN_1") (class "Default")
      (node (ref "Q4") (pin "1") (pinfunction "G_1") (pintype "passive"))
      (node (ref "U11") (pin "15") (pinfunction "LED8_15") (pintype "output"))
    )
    (net (code "19") (name "/FAN_2") (class "Default")
      (node (ref "Q5") (pin "1") (pinfunction "G_1") (pintype "passive"))
      (node (ref "U11") (pin "16") (pinfunction "LED9_16") (pintype "output"))
    )
    (net (code "20") (name "/FAN_3") (class "Default")
      (node (ref "Q6") (pin "1") (pinfunction "G_1") (pintype "passive"))
      (node (ref "U11") (pin "17") (pinfunction "LED10_17") (pintype "output"))
    )
    (net (code "21") (name "/FAULT_EXT1") (class "Default")
      (node (ref "P8") (pin "18") (pinfunction "18_18") (pintype "passive"))
      (node (ref "U16") (pin "18") (pinfunction "FAULT_18") (pintype "output"))
    )
    (net (code "22") (name "/FAULT_EXT2") (class "Default")
      (node (ref "P8") (pin "8") (pinfunction "8_8") (pintype "passive"))
      (node (ref "U17") (pin "18") (pinfunction "FAULT_18") (pintype "output"))
    )
    (net (code "23") (name "/FAULT_X") (class "Default")
      (node (ref "P8") (pin "10") (pinfunction "10_10") (pintype "passive"))
      (node (ref "U13") (pin "18") (pinfunction "FAULT_18") (pintype "output"))
    )
    (net (code "24") (name "/FAULT_Y") (class "Default")
      (node (ref "P8") (pin "9") (pinfunction "9_9") (pintype "passive"))
      (node (ref "U14") (pin "18") (pinfunction "FAULT_18") (pintype "output"))
    )
    (net (code "25") (name "/FAULT_Z") (class "Default")
      (node (ref "P9") (pin "24") (pinfunction "24_24") (pintype "passive"))
      (node (ref "U15") (pin "18") (pinfunction "FAULT_18") (pintype "output"))
    )
    (net (code "26") (name "/HEATER_EXT1") (class "Default")
      (node (ref "R47") (pin "2") (pinfunction "2_2") (pintype "passive"))
      (node (ref "U11") (pin "11") (pinfunction "LED5_11") (pintype "output"))
      (node (ref "U9") (pin "3") (pinfunction "I_3") (pintype "input"))
    )
    (net (code "27") (name "/HEATER_EXT2") (class "Default")
      (node (ref "R48") (pin "2") (pinfunction "2_2") (pintype "passive"))
      (node (ref "U11") (pin "9") (pinfunction "LED3_9") (pintype "output"))
      (node (ref "U7") (pin "3") (pinfunction "I_3") (pintype "input"))
    )
    (net (code "28") (name "/HEATER_EXT3") (class "Default")
      (node (ref "EXPAND") (pin "5") (pinfunction "5_5") (pintype "passive"))
      (node (ref "U11") (pin "18") (pinfunction "LED11_18") (pintype "output"))
    )
    (net (code "29") (name "/HEATER_EXT4") (class "Default")
      (node (ref "EXPAND") (pin "3") (pinfunction "3_3") (pintype "passive"))
      (node (ref "U11") (pin "19") (pinfunction "LED12_19") (pintype "output"))
    )
    (net (code "30") (name "/HEATER_EXT5") (class "Default")
      (node (ref "EXPAND") (pin "1") (pinfunction "1_1") (pintype "passive"))
      (node (ref "U11") (pin "20") (pinfunction "LED13_20") (pintype "output"))
    )
    (net (code "31") (name "/HEATER_HBP") (class "Default")
      (node (ref "R46") (pin "2") (pinfunction "2_2") (pintype "passive"))
      (node (ref "U11") (pin "10") (pinfunction "LED4_10") (pintype "output"))
      (node (ref "U8") (pin "3") (pinfunction "I_3") (pintype "input"))
    )
    (net (code "32") (name "/I2C2_SCL") (class "Default")
      (node (ref "P9") (pin "19") (pinfunction "19_19") (pintype "passive"))
      (node (ref "U11") (pin "26") (pinfunction "SCL_26") (pintype "input"))
      (node (ref "U18") (pin "6") (pinfunction "SCL_6") (pintype "input"))
    )
    (net (code "33") (name "/I2C2_SDA") (class "Default")
      (node (ref "P9") (pin "20") (pinfunction "20_20") (pintype "passive"))
      (node (ref "U11") (pin "27") (pinfunction "SDA_27") (pintype "bidirectional"))
      (node (ref "U18") (pin "5") (pinfunction "SDA_5") (pintype "bidirectional"))
    )
    (net (code "34") (name "/SER6") (class "Default")
      (node (ref "EXPAND") (pin "10") (pinfunction "10_10") (pintype "passive"))
      (node (ref "U5") (pin "9") (pinfunction "QH_2_9") (pintype "output"))
    )
    (net (code "35") (name "/SER_2") (class "Default")
      (node (ref "U1") (pin "9") (pinfunction "QH_2_9") (pintype "output"))
      (node (ref "U2") (pin "14") (pinfunction "SER_14") (pintype "input"))
    )
    (net (code "36") (name "/SER_3") (class "Default")
      (node (ref "U2") (pin "9") (pinfunction "QH_2_9") (pintype "output"))
      (node (ref "U3") (pin "14") (pinfunction "SER_14") (pintype "input"))
    )
    (net (code "37") (name "/SER_4") (class "Default")
      (node (ref "U3") (pin "9") (pinfunction "QH_2_9") (pintype "output"))
      (node (ref "U4") (pin "14") (pinfunction "SER_14") (pintype "input"))
    )
    (net (code "38") (name "/SER_5") (class "Default")
      (node (ref "U4") (pin "9") (pinfunction "QH_2_9") (pintype "output"))
      (node (ref "U5") (pin "14") (pinfunction "SER_14") (pintype "input"))
    )
    (net (code "39") (name "/SPI1_CS0") (class "Default")
      (node (ref "P9") (pin "28") (pinfunction "28_28") (pintype "passive"))
      (node (ref "U12") (pin "15") (pinfunction "P$15-NSYNC_15") (pintype "bidirectional"))
    )
    (net (code "40") (name "/SPI1_CS1") (class "Default")
      (node (ref "P9") (pin "42") (pinfunction "42_42") (pintype "passive"))
      (node (ref "U1") (pin "12") (pinfunction "RCLK_12") (pintype "input"))
      (node (ref "U2") (pin "12") (pinfunction "RCLK_12") (pintype "input"))
      (node (ref "U3") (pin "12") (pinfunction "RCLK_12") (pintype "input"))
      (node (ref "U4") (pin "12") (pinfunction "RCLK_12") (pintype "input"))
      (node (ref "U5") (pin "12") (pinfunction "RCLK_12") (pintype "input"))
    )
    (net (code "41") (name "/SPI1_MISO") (class "Default")
      (node (ref "P9") (pin "29") (pinfunction "29_29") (pintype "passive"))
      (node (ref "U12") (pin "2") (pinfunction "P$2-DOUT_2") (pintype "bidirectional"))
    )
    (net (code "42") (name "/SPI1_MOSI") (class "Default")
      (node (ref "P9") (pin "30") (pinfunction "30_30") (pintype "passive"))
      (node (ref "U1") (pin "14") (pinfunction "SER_14") (pintype "input"))
      (node (ref "U12") (pin "1") (pinfunction "P$1-DIN_1") (pintype "bidirectional"))
    )
    (net (code "43") (name "/SPI1_SCLK") (class "Default")
      (node (ref "P9") (pin "31") (pinfunction "31_31") (pintype "passive"))
      (node (ref "U1") (pin "11") (pinfunction "SRCLK_11") (pintype "input"))
      (node (ref "U12") (pin "16") (pinfunction "P$16-SCLK_16") (pintype "bidirectional"))
      (node (ref "U2") (pin "11") (pinfunction "SRCLK_11") (pintype "input"))
      (node (ref "U3") (pin "11") (pinfunction "SRCLK_11") (pintype "input"))
      (node (ref "U4") (pin "11") (pinfunction "SRCLK_11") (pintype "input"))
      (node (ref "U5") (pin "11") (pinfunction "SRCLK_11") (pintype "input"))
    )
    (net (code "44") (name "/STEP_EXT1") (class "Default")
      (node (ref "P9") (pin "12") (pinfunction "12_12") (pintype "passive"))
      (node (ref "U16") (pin "22") (pinfunction "STEP_22") (pintype "input"))
    )
    (net (code "45") (name "/STEP_EXT2") (class "Default")
      (node (ref "P8") (pin "11") (pinfunction "11_11") (pintype "passive"))
      (node (ref "U17") (pin "22") (pinfunction "STEP_22") (pintype "input"))
    )
    (net (code "46") (name "/STEP_X") (class "Default")
      (node (ref "P8") (pin "17") (pinfunction "17_17") (pintype "passive"))
      (node (ref "U13") (pin "22") (pinfunction "STEP_22") (pintype "input"))
    )
    (net (code "47") (name "/STEP_Y") (class "Default")
      (node (ref "P8") (pin "12") (pinfunction "12_12") (pintype "passive"))
      (node (ref "U14") (pin "22") (pinfunction "STEP_22") (pintype "input"))
    )
    (net (code "48") (name "/STEP_Z") (class "Default")
      (node (ref "P8") (pin "13") (pinfunction "13_13") (pintype "passive"))
      (node (ref "U15") (pin "22") (pinfunction "STEP_22") (pintype "input"))
    )
    (net (code "49") (name "/SYS_5V") (class "Default")
      (node (ref "P9") (pin "8") (pinfunction "8_8") (pintype "passive"))
    )
    (net (code "50") (name "/TERM_EXT1") (class "Default")
      (node (ref "C26") (pin "1") (pinfunction "1_1") (pintype "passive"))
      (node (ref "P9") (pin "33") (pinfunction "33_33") (pintype "passive"))
      (node (ref "R38") (pin "2") (pinfunction "2_2") (pintype "passive"))
    )
    (net (code "51") (name "/TERM_EXT2") (class "Default")
      (node (ref "C46") (pin "1") (pinfunction "1_1") (pintype "passive"))
      (node (ref "P9") (pin "36") (pinfunction "36_36") (pintype "passive"))
      (node (ref "R40") (pin "2") (pinfunction "2_2") (pintype "passive"))
    )
    (net (code "52") (name "/TERM_HBP") (class "Default")
      (node (ref "C45") (pin "1") (pinfunction "1_1") (pintype "passive"))
      (node (ref "P9") (pin "35") (pinfunction "35_35") (pintype "passive"))
      (node (ref "R39") (pin "2") (pinfunction "2_2") (pintype "passive"))
    )
    (net (code "53") (name "/VDD_12V") (class "Default")
      (node (ref "12V") (pin "TP") (pinfunction "TP_TP") (pintype "input"))
      (node (ref "C20") (pin "1") (pinfunction "1_1") (pintype "passive"))
      (node (ref "C21") (pin "1") (pinfunction "1_1") (pintype "passive"))
      (node (ref "C22") (pin "1") (pinfunction "1_1") (pintype "passive"))
      (node (ref "C23") (pin "1") (pinfunction "1_1") (pintype "passive"))
      (node (ref "C24") (pin "1") (pinfunction "1_1") (pintype "passive"))
      (node (ref "C25") (pin "1") (pinfunction "1_1") (pintype "passive"))
      (node (ref "C53") (pin "1") (pinfunction "1_1") (pintype "passive"))
      (node (ref "L2") (pin "P$1") (pinfunction "P$1_P$1") (pintype "passive"))
      (node (ref "R19") (pin "2") (pinfunction "2_2") (pintype "passive"))
      (node (ref "R20") (pin "2") (pinfunction "2_2") (pintype "passive"))
      (node (ref "R21") (pin "2") (pinfunction "2_2") (pintype "passive"))
      (node (ref "R42") (pin "1") (pinfunction "1_1") (pintype "passive"))
      (node (ref "U7") (pin "2") (pinfunction "VCC_2") (pintype "power_in"))
      (node (ref "U8") (pin "2") (pinfunction "VCC_2") (pintype "power_in"))
      (node (ref "U9") (pin "2") (pinfunction "VCC_2") (pintype "power_in"))
      (node (ref "X4") (pin "1") (pinfunction "S_1") (pintype "passive"))
      (node (ref "X5") (pin "1") (pinfunction "S_1") (pintype "passive"))
      (node (ref "X6") (pin "1") (pinfunction "S_1") (pintype "passive"))
    )
    (net (code "54") (name "/VDD_ADC") (class "Default")
      (node (ref "P9") (pin "32") (pinfunction "32_32") (pintype "passive"))
      (node (ref "R13") (pin "2") (pinfunction "2_2") (pintype "passive"))
      (node (ref "R17") (pin "2") (pinfunction "2_2") (pintype "passive"))
      (node (ref "R18") (pin "2") (pinfunction "2_2") (pintype "passive"))
    )
    (net (code "55") (name "/VDD_IN") (class "Default")
      (node (ref "12..24V") (pin "TP") (pinfunction "TP_TP") (pintype "input"))
      (node (ref "C10") (pin "1") (pinfunction "1_1") (pintype "passive"))
      (node (ref "C12") (pin "+") (pinfunction "+_+") (pintype "passive"))
      (node (ref "C18") (pin "1") (pinfunction "1_1") (pintype "passive"))
      (node (ref "C19") (pin "1") (pinfunction "1_1") (pintype "passive"))
      (node (ref "C2") (pin "1") (pinfunction "1_1") (pintype "passive"))
      (node (ref "C27") (pin "1") (pinfunction "1_1") (pintype "passive"))
      (node (ref "C28") (pin "1") (pinfunction "1_1") (pintype "passive"))
      (node (ref "C29") (pin "1") (pinfunction "1_1") (pintype "passive"))
      (node (ref "C30") (pin "1") (pinfunction "1_1") (pintype "passive"))
      (node (ref "C31") (pin "1") (pinfunction "1_1") (pintype "passive"))
      (node (ref "C32") (pin "1") (pinfunction "1_1") (pintype "passive"))
      (node (ref "C33") (pin "1") (pinfunction "1_1") (pintype "passive"))
      (node (ref "C34") (pin "1") (pinfunction "1_1") (pintype "passive"))
      (node (ref "C35") (pin "1") (pinfunction "1_1") (pintype "passive"))
      (node (ref "C38") (pin "1") (pinfunction "1_1") (pintype "passive"))
      (node (ref "C4") (pin "1") (pinfunction "1_1") (pintype "passive"))
      (node (ref "C42") (pin "1") (pinfunction "1_1") (pintype "passive"))
      (node (ref "C43") (pin "1") (pinfunction "1_1") (pintype "passive"))
      (node (ref "C44") (pin "1") (pinfunction "1_1") (pintype "passive"))
      (node (ref "C47") (pin "1") (pinfunction "1_1") (pintype "passive"))
      (node (ref "C48") (pin "1") (pinfunction "1_1") (pintype "passive"))
      (node (ref "C52") (pin "1") (pinfunction "1_1") (pintype "passive"))
      (node (ref "C6") (pin "1") (pinfunction "1_1") (pintype "passive"))
      (node (ref "C8") (pin "1") (pinfunction "1_1") (pintype "passive"))
      (node (ref "D1") (pin "C") (pinfunction "C_C") (pintype "passive"))
      (node (ref "D2") (pin "C") (pinfunction "C_C") (pintype "passive"))
      (node (ref "D3") (pin "C") (pinfunction "C_C") (pintype "passive"))
      (node (ref "F1") (pin "3") (pinfunction "2_3") (pintype "passive"))
      (node (ref "F1") (pin "4") (pinfunction "2_4") (pintype "passive"))
      (node (ref "R11") (pin "2") (pinfunction "2_2") (pintype "passive"))
      (node (ref "R14") (pin "2") (pinfunction "2_2") (pintype "passive"))
      (node (ref "R15") (pin "2") (pinfunction "2_2") (pintype "passive"))
      (node (ref "R16") (pin "2") (pinfunction "2_2") (pintype "passive"))
      (node (ref "R45") (pin "1") (pinfunction "1_1") (pintype "passive"))
      (node (ref "R55") (pin "2") (pinfunction "2_2") (pintype "passive"))
      (node (ref "R56") (pin "2") (pinfunction "2_2") (pintype "passive"))
      (node (ref "R57") (pin "2") (pinfunction "2_2") (pintype "passive"))
      (node (ref "U10") (pin "4") (pinfunction "VIN_4") (pintype "power_in"))
      (node (ref "U13") (pin "11") (pinfunction "VMB_11") (pintype "power_in"))
      (node (ref "U13") (pin "4") (pinfunction "VMA_4") (pintype "power_in"))
      (node (ref "U14") (pin "11") (pinfunction "VMB_11") (pintype "power_in"))
      (node (ref "U14") (pin "4") (pinfunction "VMA_4") (pintype "power_in"))
      (node (ref "U15") (pin "11") (pinfunction "VMB_11") (pintype "power_in"))
      (node (ref "U15") (pin "4") (pinfunction "VMA_4") (pintype "power_in"))
      (node (ref "U16") (pin "11") (pinfunction "VMB_11") (pintype "power_in"))
      (node (ref "U16") (pin "4") (pinfunction "VMA_4") (pintype "power_in"))
      (node (ref "U17") (pin "11") (pinfunction "VMB_11") (pintype "power_in"))
      (node (ref "U17") (pin "4") (pinfunction "VMA_4") (pintype "power_in"))
      (node (ref "U6") (pin "11") (pinfunction "VIN_11") (pintype "power_in"))
      (node (ref "U6") (pin "2") (pinfunction "VIN_2") (pintype "power_in"))
      (node (ref "U6") (pin "3") (pinfunction "VIN_3") (pintype "power_in"))
      (node (ref "X20") (pin "1") (pinfunction "1_1") (pintype "passive"))
      (node (ref "X20") (pin "2") (pinfunction "1_2") (pintype "passive"))
      (node (ref "X21") (pin "1") (pinfunction "1_1") (pintype "passive"))
      (node (ref "X3") (pin "1") (pinfunction "1_1") (pintype "passive"))
    )
    (net (code "56") (name "/VIN") (class "Default")
      (node (ref "F1") (pin "1") (pinfunction "1_1") (pintype "passive"))
      (node (ref "F1") (pin "2") (pinfunction "1_2") (pintype "passive"))
      (node (ref "LED8") (pin "A") (pinfunction "A_A") (pintype "passive"))
      (node (ref "X2") (pin "3") (pinfunction "1_3") (pintype "passive"))
      (node (ref "X2") (pin "4") (pinfunction "1_4") (pintype "passive"))
    )
    (net (code "57") (name "/VREF_EXT1") (class "Default")
      (node (ref "U12") (pin "6") (pinfunction "P$6-VOUTD_6") (pintype "bidirectional"))
      (node (ref "U16") (pin "12") (pinfunction "AVREF_12") (pintype "input"))
      (node (ref "U16") (pin "13") (pinfunction "BVREF_13") (pintype "input"))
    )
    (net (code "58") (name "/VREF_EXT2") (class "Default")
      (node (ref "U12") (pin "14") (pinfunction "P$14-VOUTE_14") (pintype "bidirectional"))
      (node (ref "U17") (pin "12") (pinfunction "AVREF_12") (pintype "input"))
      (node (ref "U17") (pin "13") (pinfunction "BVREF_13") (pintype "input"))
    )
    (net (code "59") (name "/VREF_EXT3") (class "Default")
      (node (ref "EXPAND") (pin "2") (pinfunction "2_2") (pintype "passive"))
      (node (ref "U12") (pin "13") (pinfunction "P$13-VOUTF_13") (pintype "bidirectional"))
    )
    (net (code "60") (name "/VREF_EXT4") (class "Default")
      (node (ref "EXPAND") (pin "4") (pinfunction "4_4") (pintype "passive"))
      (node (ref "U12") (pin "12") (pinfunction "P$12-VOUTG_12") (pintype "bidirectional"))
    )
    (net (code "61") (name "/VREF_EXT5") (class "Default")
      (node (ref "EXPAND") (pin "6") (pinfunction "6_6") (pintype "passive"))
      (node (ref "U12") (pin "11") (pinfunction "P$11-VOUTH_11") (pintype "bidirectional"))
    )
    (net (code "62") (name "/VREF_X") (class "Default")
      (node (ref "U12") (pin "3") (pinfunction "P$3-VOUTA_3") (pintype "bidirectional"))
      (node (ref "U13") (pin "12") (pinfunction "AVREF_12") (pintype "input"))
      (node (ref "U13") (pin "13") (pinfunction "BVREF_13") (pintype "input"))
    )
    (net (code "63") (name "/VREF_Y") (class "Default")
      (node (ref "U12") (pin "4") (pinfunction "P$4-VOUTB_4") (pintype "bidirectional"))
      (node (ref "U14") (pin "12") (pinfunction "AVREF_12") (pintype "input"))
      (node (ref "U14") (pin "13") (pinfunction "BVREF_13") (pintype "input"))
    )
    (net (code "64") (name "/VREF_Z") (class "Default")
      (node (ref "U12") (pin "5") (pinfunction "P$5-VOUTC_5") (pintype "bidirectional"))
      (node (ref "U15") (pin "12") (pinfunction "AVREF_12") (pintype "input"))
      (node (ref "U15") (pin "13") (pinfunction "BVREF_13") (pintype "input"))
    )
    (net (code "65") (name "AGND") (class "Default")
      (node (ref "C14") (pin "2") (pinfunction "2_2") (pintype "passive"))
      (node (ref "C15") (pin "2") (pinfunction "2_2") (pintype "passive"))
      (node (ref "C16") (pin "2") (pinfunction "2_2") (pintype "passive"))
      (node (ref "C26") (pin "2") (pinfunction "2_2") (pintype "passive"))
      (node (ref "C45") (pin "2") (pinfunction "2_2") (pintype "passive"))
      (node (ref "C46") (pin "2") (pinfunction "2_2") (pintype "passive"))
      (node (ref "P9") (pin "34") (pinfunction "34_34") (pintype "passive"))
      (node (ref "X7") (pin "2") (pinfunction "S_2") (pintype "passive"))
      (node (ref "X8") (pin "2") (pinfunction "S_2") (pintype "passive"))
      (node (ref "X9") (pin "2") (pinfunction "S_2") (pintype "passive"))
    )
    (net (code "66") (name "GND") (class "Default")
      (node (ref "C11") (pin "2") (pinfunction "2_2") (pintype "passive"))
      (node (ref "C12") (pin "-") (pinfunction "-_-") (pintype "passive"))
      (node (ref "C13") (pin "2") (pinfunction "2_2") (pintype "passive"))
      (node (ref "C17") (pin "2") (pinfunction "2_2") (pintype "passive"))
      (node (ref "C18") (pin "2") (pinfunction "2_2") (pintype "passive"))
      (node (ref "C19") (pin "2") (pinfunction "2_2") (pintype "passive"))
      (node (ref "C20") (pin "2") (pinfunction "2_2") (pintype "passive"))
      (node (ref "C21") (pin "2") (pinfunction "2_2") (pintype "passive"))
      (node (ref "C22") (pin "2") (pinfunction "2_2") (pintype "passive"))
      (node (ref "C23") (pin "2") (pinfunction "2_2") (pintype "passive"))
      (node (ref "C24") (pin "2") (pinfunction "2_2") (pintype "passive"))
      (node (ref "C25") (pin "2") (pinfunction "2_2") (pintype "passive"))
      (node (ref "C27") (pin "2") (pinfunction "2_2") (pintype "passive"))
      (node (ref "C28") (pin "2") (pinfunction "2_2") (pintype "passive"))
      (node (ref "C29") (pin "2") (pinfunction "2_2") (pintype "passive"))
      (node (ref "C30") (pin "2") (pinfunction "2_2") (pintype "passive"))
      (node (ref "C31") (pin "2") (pinfunction "2_2") (pintype "passive"))
      (node (ref "C32") (pin "2") (pinfunction "2_2") (pintype "passive"))
      (node (ref "C33") (pin "2") (pinfunction "2_2") (pintype "passive"))
      (node (ref "C34") (pin "2") (pinfunction "2_2") (pintype "passive"))
      (node (ref "C35") (pin "2") (pinfunction "2_2") (pintype "passive"))
      (node (ref "C36") (pin "2") (pinfunction "2_2") (pintype "passive"))
      (node (ref "C37") (pin "2") (pinfunction "2_2") (pintype "passive"))
      (node (ref "C38") (pin "2") (pinfunction "2_2") (pintype "passive"))
      (node (ref "C39") (pin "2") (pinfunction "2_2") (pintype "passive"))
      (node (ref "C40") (pin "2") (pinfunction "2_2") (pintype "passive"))
      (node (ref "C41") (pin "2") (pinfunction "2_2") (pintype "passive"))
      (node (ref "C42") (pin "2") (pinfunction "2_2") (pintype "passive"))
      (node (ref "C43") (pin "2") (pinfunction "2_2") (pintype "passive"))
      (node (ref "C44") (pin "2") (pinfunction "2_2") (pintype "passive"))
      (node (ref "C47") (pin "2") (pinfunction "2_2") (pintype "passive"))
      (node (ref "C48") (pin "2") (pinfunction "2_2") (pintype "passive"))
      (node (ref "C49") (pin "2") (pinfunction "2_2") (pintype "passive"))
      (node (ref "C50") (pin "2") (pinfunction "2_2") (pintype "passive"))
      (node (ref "C52") (pin "2") (pinfunction "2_2") (pintype "passive"))
      (node (ref "C53") (pin "2") (pinfunction "2_2") (pintype "passive"))
      (node (ref "C54") (pin "2") (pinfunction "2_2") (pintype "passive"))
      (node (ref "C57") (pin "2") (pinfunction "2_2") (pintype "passive"))
      (node (ref "C58") (pin "2") (pinfunction "2_2") (pintype "passive"))
      (node (ref "C59") (pin "2") (pinfunction "2_2") (pintype "passive"))
      (node (ref "C60") (pin "2") (pinfunction "2_2") (pintype "passive"))
      (node (ref "D4") (pin "A") (pinfunction "A_A") (pintype "passive"))
      (node (ref "LED4") (pin "C") (pinfunction "C_C") (pintype "passive"))
      (node (ref "P8") (pin "1") (pinfunction "1_1") (pintype "passive"))
      (node (ref "P8") (pin "2") (pinfunction "2_2") (pintype "passive"))
      (node (ref "P9") (pin "1") (pinfunction "1_1") (pintype "passive"))
      (node (ref "P9") (pin "2") (pinfunction "2_2") (pintype "passive"))
      (node (ref "P9") (pin "43") (pinfunction "43_43") (pintype "passive"))
      (node (ref "P9") (pin "44") (pinfunction "44_44") (pintype "passive"))
      (node (ref "P9") (pin "45") (pinfunction "45_45") (pintype "passive"))
      (node (ref "P9") (pin "46") (pinfunction "46_46") (pintype "passive"))
      (node (ref "Q1") (pin "1") (pinfunction "S_1") (pintype "passive"))
      (node (ref "Q1") (pin "2") (pinfunction "S_2") (pintype "passive"))
      (node (ref "Q1") (pin "3") (pinfunction "S_3") (pintype "passive"))
      (node (ref "Q2") (pin "1") (pinfunction "S_1") (pintype "passive"))
      (node (ref "Q2") (pin "2") (pinfunction "S_2") (pintype "passive"))
      (node (ref "Q2") (pin "3") (pinfunction "S_3") (pintype "passive"))
      (node (ref "Q3") (pin "1") (pinfunction "S_1") (pintype "passive"))
      (node (ref "Q3") (pin "2") (pinfunction "S_2") (pintype "passive"))
      (node (ref "Q3") (pin "3") (pinfunction "S_3") (pintype "passive"))
      (node (ref "Q4") (pin "3") (pinfunction "S_3") (pintype "passive"))
      (node (ref "Q5") (pin "3") (pinfunction "S_3") (pintype "passive"))
      (node (ref "Q6") (pin "3") (pinfunction "S_3") (pintype "passive"))
      (node (ref "R1") (pin "1") (pinfunction "1_1") (pintype "passive"))
      (node (ref "R10") (pin "1") (pinfunction "1_1") (pintype "passive"))
      (node (ref "R2") (pin "1") (pinfunction "1_1") (pintype "passive"))
      (node (ref "R3") (pin "1") (pinfunction "1_1") (pintype "passive"))
      (node (ref "R4") (pin "1") (pinfunction "1_1") (pintype "passive"))
      (node (ref "R43") (pin "2") (pinfunction "2_2") (pintype "passive"))
      (node (ref "R44") (pin "2") (pinfunction "2_2") (pintype "passive"))
      (node (ref "R46") (pin "1") (pinfunction "1_1") (pintype "passive"))
      (node (ref "R47") (pin "1") (pinfunction "1_1") (pintype "passive"))
      (node (ref "R48") (pin "1") (pinfunction "1_1") (pintype "passive"))
      (node (ref "R5") (pin "1") (pinfunction "1_1") (pintype "passive"))
      (node (ref "R6") (pin "1") (pinfunction "1_1") (pintype "passive"))
      (node (ref "R7") (pin "1") (pinfunction "1_1") (pintype "passive"))
      (node (ref "R8") (pin "1") (pinfunction "1_1") (pintype "passive"))
      (node (ref "R9") (pin "1") (pinfunction "1_1") (pintype "passive"))
      (node (ref "S2") (pin "1") (pinfunction "1_1") (pintype "passive"))
      (node (ref "S2") (pin "2") (pinfunction "2_2") (pintype "passive"))
      (node (ref "U1") (pin "13") (pinfunction "~{OE}_13") (pintype "input"))
      (node (ref "U1") (pin "8") (pinfunction "GND_8") (pintype "passive"))
      (node (ref "U10") (pin "6") (pinfunction "GND_6") (pintype "power_in"))
      (node (ref "U10") (pin "EP") (pinfunction "EP_EP") (pintype "power_in"))
      (node (ref "U11") (pin "14") (pinfunction "VSS_14") (pintype "passive"))
      (node (ref "U11") (pin "23") (pinfunction "~{OE}_23") (pintype "input"))
      (node (ref "U12") (pin "10") (pinfunction "P$10-GND_10") (pintype "bidirectional"))
      (node (ref "U13") (pin "14") (pinfunction "GND_0_14") (pintype "power_in"))
      (node (ref "U13") (pin "28") (pinfunction "GND_1_28") (pintype "power_in"))
      (node (ref "U13") (pin "EXP") (pinfunction "GND_PAD_EXP") (pintype "power_in"))
      (node (ref "U14") (pin "14") (pinfunction "GND_0_14") (pintype "power_in"))
      (node (ref "U14") (pin "28") (pinfunction "GND_1_28") (pintype "power_in"))
      (node (ref "U14") (pin "EXP") (pinfunction "GND_PAD_EXP") (pintype "power_in"))
      (node (ref "U15") (pin "14") (pinfunction "GND_0_14") (pintype "power_in"))
      (node (ref "U15") (pin "28") (pinfunction "GND_1_28") (pintype "power_in"))
      (node (ref "U15") (pin "EXP") (pinfunction "GND_PAD_EXP") (pintype "power_in"))
      (node (ref "U16") (pin "14") (pinfunction "GND_0_14") (pintype "power_in"))
      (node (ref "U16") (pin "28") (pinfunction "GND_1_28") (pintype "power_in"))
      (node (ref "U16") (pin "EXP") (pinfunction "GND_PAD_EXP") (pintype "power_in"))
      (node (ref "U17") (pin "14") (pinfunction "GND_0_14") (pintype "power_in"))
      (node (ref "U17") (pin "28") (pinfunction "GND_1_28") (pintype "power_in"))
      (node (ref "U17") (pin "EXP") (pinfunction "GND_PAD_EXP") (pintype "power_in"))
      (node (ref "U18") (pin "4") (pinfunction "GND_4") (pintype "power_in"))
      (node (ref "U2") (pin "13") (pinfunction "~{OE}_13") (pintype "input"))
      (node (ref "U2") (pin "8") (pinfunction "GND_8") (pintype "passive"))
      (node (ref "U3") (pin "13") (pinfunction "~{OE}_13") (pintype "input"))
      (node (ref "U3") (pin "8") (pinfunction "GND_8") (pintype "passive"))
      (node (ref "U4") (pin "13") (pinfunction "~{OE}_13") (pintype "input"))
      (node (ref "U4") (pin "8") (pinfunction "GND_8") (pintype "passive"))
      (node (ref "U5") (pin "13") (pinfunction "~{OE}_13") (pintype "input"))
      (node (ref "U5") (pin "8") (pinfunction "GND_8") (pintype "passive"))
      (node (ref "U6") (pin "14") (pinfunction "PGND_14") (pintype "power_in"))
      (node (ref "U6") (pin "15") (pinfunction "PGND_15") (pintype "power_in"))
      (node (ref "U6") (pin "4") (pinfunction "SGND_4") (pintype "power_in"))
      (node (ref "U6") (pin "P$17") (pinfunction "EP_P$17") (pintype "power_in"))
      (node (ref "U7") (pin "1") (pinfunction "GND_1") (pintype "power_in"))
      (node (ref "U7") (pin "4") (pinfunction "GND_4") (pintype "power_in"))
      (node (ref "U8") (pin "1") (pinfunction "GND_1") (pintype "power_in"))
      (node (ref "U8") (pin "4") (pinfunction "GND_4") (pintype "power_in"))
      (node (ref "U9") (pin "1") (pinfunction "GND_1") (pintype "power_in"))
      (node (ref "U9") (pin "4") (pinfunction "GND_4") (pintype "power_in"))
      (node (ref "X1") (pin "1") (pinfunction "S_1") (pintype "passive"))
      (node (ref "X10") (pin "1") (pinfunction "S_1") (pintype "passive"))
      (node (ref "X11") (pin "1") (pinfunction "S_1") (pintype "passive"))
      (node (ref "X12") (pin "3") (pinfunction "S_3") (pintype "passive"))
      (node (ref "X13") (pin "1") (pinfunction "S_1") (pintype "passive"))
      (node (ref "X19") (pin "1") (pinfunction "S_1") (pintype "passive"))
      (node (ref "X2") (pin "1") (pinfunction "1_1") (pintype "passive"))
      (node (ref "X2") (pin "2") (pinfunction "1_2") (pintype "passive"))
      (node (ref "X23") (pin "1") (pinfunction "S_1") (pintype "passive"))
      (node (ref "X7") (pin "3") (pinfunction "S_3") (pintype "passive"))
      (node (ref "X8") (pin "3") (pinfunction "S_3") (pintype "passive"))
      (node (ref "X9") (pin "3") (pinfunction "S_3") (pintype "passive"))
    )
    (net (code "67") (name "Net-(C51-Pad1)") (class "Default")
      (node (ref "C51") (pin "1") (pinfunction "1_1") (pintype "passive"))
      (node (ref "R58") (pin "1") (pinfunction "1_1") (pintype "passive"))
    )
    (net (code "68") (name "Net-(C51-Pad2)") (class "Default")
      (node (ref "C51") (pin "2") (pinfunction "2_2") (pintype "passive"))
      (node (ref "L1") (pin "1") (pinfunction "1_1") (pintype "passive"))
      (node (ref "U6") (pin "1") (pinfunction "SW_1") (pintype "power_in"))
      (node (ref "U6") (pin "12") (pinfunction "SW_12") (pintype "power_in"))
      (node (ref "U6") (pin "13") (pinfunction "SW_13") (pintype "power_in"))
      (node (ref "U6") (pin "16") (pinfunction "SW_16") (pintype "power_in"))
    )
    (net (code "69") (name "Net-(C56-Pad2)") (class "Default")
      (node (ref "C56") (pin "2") (pinfunction "2_2") (pintype "passive"))
      (node (ref "R44") (pin "1") (pinfunction "1_1") (pintype "passive"))
    )
    (net (code "70") (name "Net-(LED1-PadA)") (class "Default")
      (node (ref "LED1") (pin "A") (pinfunction "A_A") (pintype "passive"))
      (node (ref "R14") (pin "1") (pinfunction "1_1") (pintype "passive"))
    )
    (net (code "71") (name "Net-(LED2-PadA)") (class "Default")
      (node (ref "LED2") (pin "A") (pinfunction "A_A") (pintype "passive"))
      (node (ref "R16") (pin "1") (pinfunction "1_1") (pintype "passive"))
    )
    (net (code "72") (name "Net-(LED3-PadA)") (class "Default")
      (node (ref "LED3") (pin "A") (pinfunction "A_A") (pintype "passive"))
      (node (ref "R15") (pin "1") (pinfunction "1_1") (pintype "passive"))
    )
    (net (code "73") (name "Net-(LED4-PadA)") (class "Default")
      (node (ref "LED4") (pin "A") (pinfunction "A_A") (pintype "passive"))
      (node (ref "R11") (pin "1") (pinfunction "1_1") (pintype "passive"))
    )
    (net (code "74") (name "Net-(LED5-PadA)") (class "Default")
      (node (ref "LED5") (pin "A") (pinfunction "A_A") (pintype "passive"))
      (node (ref "R19") (pin "1") (pinfunction "1_1") (pintype "passive"))
    )
    (net (code "75") (name "Net-(LED6-PadA)") (class "Default")
      (node (ref "LED6") (pin "A") (pinfunction "A_A") (pintype "passive"))
      (node (ref "R20") (pin "1") (pinfunction "1_1") (pintype "passive"))
    )
    (net (code "76") (name "Net-(LED7-PadA)") (class "Default")
      (node (ref "LED7") (pin "A") (pinfunction "A_A") (pintype "passive"))
      (node (ref "R21") (pin "1") (pinfunction "1_1") (pintype "passive"))
    )
    (net (code "77") (name "Net-(LED8-PadC)") (class "Default")
      (node (ref "LED8") (pin "C") (pinfunction "C_C") (pintype "passive"))
      (node (ref "R45") (pin "2") (pinfunction "2_2") (pintype "passive"))
    )
    (net (code "78") (name "Net-(Q1-G)") (class "Default")
      (node (ref "Q1") (pin "4") (pinfunction "G_4") (pintype "passive"))
      (node (ref "R31") (pin "1") (pinfunction "1_1") (pintype "passive"))
    )
    (net (code "79") (name "Net-(Q2-G)") (class "Default")
      (node (ref "Q2") (pin "4") (pinfunction "G_4") (pintype "passive"))
      (node (ref "R37") (pin "1") (pinfunction "1_1") (pintype "passive"))
    )
    (net (code "80") (name "Net-(Q3-G)") (class "Default")
      (node (ref "Q3") (pin "4") (pinfunction "G_4") (pintype "passive"))
      (node (ref "R32") (pin "1") (pinfunction "1_1") (pintype "passive"))
    )
    (net (code "81") (name "Net-(U1-QB)") (class "Default")
      (node (ref "U1") (pin "1") (pinfunction "QB_1") (pintype "output"))
      (node (ref "U13") (pin "26") (pinfunction "MODE2_26") (pintype "input"))
    )
    (net (code "82") (name "Net-(U1-QC)") (class "Default")
      (node (ref "U1") (pin "2") (pinfunction "QC_2") (pintype "output"))
      (node (ref "U13") (pin "25") (pinfunction "MODE1_25") (pintype "input"))
    )
    (net (code "83") (name "Net-(U1-QD)") (class "Default")
      (node (ref "U1") (pin "3") (pinfunction "QD_3") (pintype "output"))
      (node (ref "U13") (pin "24") (pinfunction "MODE0_24") (pintype "input"))
    )
    (net (code "84") (name "Net-(U1-QE)") (class "Default")
      (node (ref "U1") (pin "4") (pinfunction "QE_4") (pintype "output"))
      (node (ref "U13") (pin "21") (pinfunction "ENBL_21") (pintype "input"))
    )
    (net (code "85") (name "Net-(U1-QF)") (class "Default")
      (node (ref "U1") (pin "5") (pinfunction "QF_5") (pintype "output"))
      (node (ref "U13") (pin "19") (pinfunction "DECAY_19") (pintype "input"))
    )
    (net (code "86") (name "Net-(U1-QG)") (class "Default")
      (node (ref "U1") (pin "6") (pinfunction "QG_6") (pintype "output"))
      (node (ref "U13") (pin "17") (pinfunction "SLEEP_17") (pintype "input"))
    )
    (net (code "87") (name "Net-(U1-QH)") (class "Default")
      (node (ref "U1") (pin "7") (pinfunction "QH_7") (pintype "output"))
      (node (ref "U13") (pin "16") (pinfunction "RESET_16") (pintype "input"))
    )
    (net (code "88") (name "Net-(U1-~{SRCLR})") (class "Default")
      (node (ref "R12") (pin "1") (pinfunction "1_1") (pintype "passive"))
      (node (ref "U1") (pin "10") (pinfunction "~{SRCLR}_10") (pintype "input"))
    )
    (net (code "89") (name "Net-(U2-~{SRCLR})") (class "Default")
      (node (ref "R35") (pin "1") (pinfunction "1_1") (pintype "passive"))
      (node (ref "U2") (pin "10") (pinfunction "~{SRCLR}_10") (pintype "input"))
    )
    (net (code "90") (name "Net-(U3-~{SRCLR})") (class "Default")
      (node (ref "R36") (pin "1") (pinfunction "1_1") (pintype "passive"))
      (node (ref "U3") (pin "10") (pinfunction "~{SRCLR}_10") (pintype "input"))
    )
    (net (code "91") (name "Net-(U4-~{SRCLR})") (class "Default")
      (node (ref "R33") (pin "1") (pinfunction "1_1") (pintype "passive"))
      (node (ref "U4") (pin "10") (pinfunction "~{SRCLR}_10") (pintype "input"))
    )
    (net (code "92") (name "Net-(U5-~{SRCLR})") (class "Default")
      (node (ref "R34") (pin "1") (pinfunction "1_1") (pintype "passive"))
      (node (ref "U5") (pin "10") (pinfunction "~{SRCLR}_10") (pintype "input"))
    )
    (net (code "93") (name "Net-(U6-BOOST)") (class "Default")
      (node (ref "R58") (pin "2") (pinfunction "2_2") (pintype "passive"))
      (node (ref "U6") (pin "10") (pinfunction "BOOST_10") (pintype "bidirectional"))
    )
    (net (code "94") (name "Net-(U6-PG)") (class "Default")
      (node (ref "R41") (pin "1") (pinfunction "1_1") (pintype "passive"))
      (node (ref "U6") (pin "8") (pinfunction "PG_8") (pintype "output"))
    )
    (net (code "95") (name "Net-(U7-O)") (class "Default")
      (node (ref "R37") (pin "2") (pinfunction "2_2") (pintype "passive"))
      (node (ref "U7") (pin "5") (pinfunction "O_5") (pintype "output"))
    )
    (net (code "96") (name "Net-(U8-O)") (class "Default")
      (node (ref "R31") (pin "2") (pinfunction "2_2") (pintype "passive"))
      (node (ref "U8") (pin "5") (pinfunction "O_5") (pintype "output"))
    )
    (net (code "97") (name "Net-(U9-O)") (class "Default")
      (node (ref "R32") (pin "2") (pinfunction "2_2") (pintype "passive"))
      (node (ref "U9") (pin "5") (pinfunction "O_5") (pintype "output"))
    )
    (net (code "98") (name "Net-(U10-BOOT)") (class "Default")
      (node (ref "C55") (pin "1") (pinfunction "1_1") (pintype "passive"))
      (node (ref "U10") (pin "2") (pinfunction "BOOT_2") (pintype "input"))
    )
    (net (code "99") (name "Net-(U10-COMP)") (class "Default")
      (node (ref "C56") (pin "1") (pinfunction "1_1") (pintype "passive"))
      (node (ref "U10") (pin "8") (pinfunction "COMP_8") (pintype "bidirectional"))
    )
    (net (code "100") (name "Net-(U10-FB)") (class "Default")
      (node (ref "R42") (pin "2") (pinfunction "2_2") (pintype "passive"))
      (node (ref "R43") (pin "1") (pinfunction "1_1") (pintype "passive"))
      (node (ref "U10") (pin "7") (pinfunction "FB_7") (pintype "input"))
    )
    (net (code "101") (name "Net-(U10-SS)") (class "Default")
      (node (ref "C54") (pin "1") (pinfunction "1_1") (pintype "passive"))
      (node (ref "U10") (pin "10") (pinfunction "SS_10") (pintype "bidirectional"))
    )
    (net (code "102") (name "Net-(U10-SW)") (class "Default")
      (node (ref "C55") (pin "2") (pinfunction "2_2") (pintype "passive"))
      (node (ref "D4") (pin "C") (pinfunction "C_C") (pintype "passive"))
      (node (ref "L2") (pin "P$2") (pinfunction "P$2_P$2") (pintype "passive"))
      (node (ref "U10") (pin "5") (pinfunction "SW_5") (pintype "power_in"))
    )
    (net (code "103") (name "Net-(U11-A0)") (class "Default")
      (node (ref "R27") (pin "1") (pinfunction "1_1") (pintype "passive"))
      (node (ref "U11") (pin "1") (pinfunction "A0_1") (pintype "input"))
    )
    (net (code "104") (name "Net-(U11-A1)") (class "Default")
      (node (ref "R26") (pin "1") (pinfunction "1_1") (pintype "passive"))
      (node (ref "U11") (pin "2") (pinfunction "A1_2") (pintype "input"))
    )
    (net (code "105") (name "Net-(U11-A2)") (class "Default")
      (node (ref "R25") (pin "1") (pinfunction "1_1") (pintype "passive"))
      (node (ref "U11") (pin "3") (pinfunction "A2_3") (pintype "input"))
    )
    (net (code "106") (name "Net-(U11-A3)") (class "Default")
      (node (ref "R28") (pin "1") (pinfunction "1_1") (pintype "passive"))
      (node (ref "U11") (pin "4") (pinfunction "A3_4") (pintype "input"))
    )
    (net (code "107") (name "Net-(U11-A4)") (class "Default")
      (node (ref "R29") (pin "1") (pinfunction "1_1") (pintype "passive"))
      (node (ref "U11") (pin "5") (pinfunction "A4_5") (pintype "input"))
    )
    (net (code "108") (name "Net-(U11-A5)") (class "Default")
      (node (ref "R30") (pin "1") (pinfunction "1_1") (pintype "passive"))
      (node (ref "U11") (pin "24") (pinfunction "A5_24") (pintype "input"))
    )
    (net (code "109") (name "Net-(U13-AOUT1)") (class "Default")
      (node (ref "U13") (pin "5") (pinfunction "AOUT1_5") (pintype "output"))
      (node (ref "X14") (pin "4") (pinfunction "S_4") (pintype "passive"))
    )
    (net (code "110") (name "Net-(U13-AOUT2)") (class "Default")
      (node (ref "U13") (pin "7") (pinfunction "AOUT2_7") (pintype "output"))
      (node (ref "X14") (pin "3") (pinfunction "S_3") (pintype "passive"))
    )
    (net (code "111") (name "Net-(U13-BOUT1)") (class "Default")
      (node (ref "U13") (pin "10") (pinfunction "BOUT1_10") (pintype "output"))
      (node (ref "X14") (pin "1") (pinfunction "S_1") (pintype "passive"))
    )
    (net (code "112") (name "Net-(U13-BOUT2)") (class "Default")
      (node (ref "U13") (pin "8") (pinfunction "BOUT2_8") (pintype "output"))
      (node (ref "X14") (pin "2") (pinfunction "S_2") (pintype "passive"))
    )
    (net (code "113") (name "Net-(U13-CP1)") (class "Default")
      (node (ref "C1") (pin "2") (pinfunction "2_2") (pintype "passive"))
      (node (ref "U13") (pin "1") (pinfunction "CP1_1") (pintype "bidirectional"))
    )
    (net (code "114") (name "Net-(U13-CP2)") (class "Default")
      (node (ref "C1") (pin "1") (pinfunction "1_1") (pintype "passive"))
      (node (ref "U13") (pin "2") (pinfunction "CP2_2") (pintype "bidirectional"))
    )
    (net (code "115") (name "Net-(U13-ISENA)") (class "Default")
      (node (ref "R2") (pin "2") (pinfunction "2_2") (pintype "passive"))
      (node (ref "U13") (pin "6") (pinfunction "ISENA_6") (pintype "output"))
    )
    (net (code "116") (name "Net-(U13-ISENB)") (class "Default")
      (node (ref "R1") (pin "2") (pinfunction "2_2") (pintype "passive"))
      (node (ref "U13") (pin "9") (pinfunction "ISENB_9") (pintype "output"))
    )
    (net (code "117") (name "Net-(U13-VCP)") (class "Default")
      (node (ref "C2") (pin "2") (pinfunction "2_2") (pintype "passive"))
      (node (ref "U13") (pin "3") (pinfunction "VCP_3") (pintype "bidirectional"))
    )
    (net (code "118") (name "Net-(U14-AOUT1)") (class "Default")
      (node (ref "U14") (pin "5") (pinfunction "AOUT1_5") (pintype "output"))
      (node (ref "X15") (pin "4") (pinfunction "S_4") (pintype "passive"))
    )
    (net (code "119") (name "Net-(U14-AOUT2)") (class "Default")
      (node (ref "U14") (pin "7") (pinfunction "AOUT2_7") (pintype "output"))
      (node (ref "X15") (pin "3") (pinfunction "S_3") (pintype "passive"))
    )
    (net (code "120") (name "Net-(U14-BOUT1)") (class "Default")
      (node (ref "U14") (pin "10") (pinfunction "BOUT1_10") (pintype "output"))
      (node (ref "X15") (pin "1") (pinfunction "S_1") (pintype "passive"))
    )
    (net (code "121") (name "Net-(U14-BOUT2)") (class "Default")
      (node (ref "U14") (pin "8") (pinfunction "BOUT2_8") (pintype "output"))
      (node (ref "X15") (pin "2") (pinfunction "S_2") (pintype "passive"))
    )
    (net (code "122") (name "Net-(U14-CP1)") (class "Default")
      (node (ref "C3") (pin "2") (pinfunction "2_2") (pintype "passive"))
      (node (ref "U14") (pin "1") (pinfunction "CP1_1") (pintype "bidirectional"))
    )
    (net (code "123") (name "Net-(U14-CP2)") (class "Default")
      (node (ref "C3") (pin "1") (pinfunction "1_1") (pintype "passive"))
      (node (ref "U14") (pin "2") (pinfunction "CP2_2") (pintype "bidirectional"))
    )
    (net (code "124") (name "Net-(U14-DECAY)") (class "Default")
      (node (ref "U14") (pin "19") (pinfunction "DECAY_19") (pintype "input"))
      (node (ref "U2") (pin "5") (pinfunction "QF_5") (pintype "output"))
    )
    (net (code "125") (name "Net-(U14-ENBL)") (class "Default")
      (node (ref "U14") (pin "21") (pinfunction "ENBL_21") (pintype "input"))
      (node (ref "U2") (pin "4") (pinfunction "QE_4") (pintype "output"))
    )
    (net (code "126") (name "Net-(U14-ISENA)") (class "Default")
      (node (ref "R4") (pin "2") (pinfunction "2_2") (pintype "passive"))
      (node (ref "U14") (pin "6") (pinfunction "ISENA_6") (pintype "output"))
    )
    (net (code "127") (name "Net-(U14-ISENB)") (class "Default")
      (node (ref "R3") (pin "2") (pinfunction "2_2") (pintype "passive"))
      (node (ref "U14") (pin "9") (pinfunction "ISENB_9") (pintype "output"))
    )
    (net (code "128") (name "Net-(U14-MODE0)") (class "Default")
      (node (ref "U14") (pin "24") (pinfunction "MODE0_24") (pintype "input"))
      (node (ref "U2") (pin "3") (pinfunction "QD_3") (pintype "output"))
    )
    (net (code "129") (name "Net-(U14-MODE1)") (class "Default")
      (node (ref "U14") (pin "25") (pinfunction "MODE1_25") (pintype "input"))
      (node (ref "U2") (pin "2") (pinfunction "QC_2") (pintype "output"))
    )
    (net (code "130") (name "Net-(U14-MODE2)") (class "Default")
      (node (ref "U14") (pin "26") (pinfunction "MODE2_26") (pintype "input"))
      (node (ref "U2") (pin "1") (pinfunction "QB_1") (pintype "output"))
    )
    (net (code "131") (name "Net-(U14-RESET)") (class "Default")
      (node (ref "U14") (pin "16") (pinfunction "RESET_16") (pintype "input"))
      (node (ref "U2") (pin "7") (pinfunction "QH_7") (pintype "output"))
    )
    (net (code "132") (name "Net-(U14-SLEEP)") (class "Default")
      (node (ref "U14") (pin "17") (pinfunction "SLEEP_17") (pintype "input"))
      (node (ref "U2") (pin "6") (pinfunction "QG_6") (pintype "output"))
    )
    (net (code "133") (name "Net-(U14-VCP)") (class "Default")
      (node (ref "C4") (pin "2") (pinfunction "2_2") (pintype "passive"))
      (node (ref "U14") (pin "3") (pinfunction "VCP_3") (pintype "bidirectional"))
    )
    (net (code "134") (name "Net-(U15-AOUT1)") (class "Default")
      (node (ref "U15") (pin "5") (pinfunction "AOUT1_5") (pintype "output"))
      (node (ref "X16") (pin "4") (pinfunction "S_4") (pintype "passive"))
    )
    (net (code "135") (name "Net-(U15-AOUT2)") (class "Default")
      (node (ref "U15") (pin "7") (pinfunction "AOUT2_7") (pintype "output"))
      (node (ref "X16") (pin "3") (pinfunction "S_3") (pintype "passive"))
    )
    (net (code "136") (name "Net-(U15-BOUT1)") (class "Default")
      (node (ref "U15") (pin "10") (pinfunction "BOUT1_10") (pintype "output"))
      (node (ref "X16") (pin "1") (pinfunction "S_1") (pintype "passive"))
    )
    (net (code "137") (name "Net-(U15-BOUT2)") (class "Default")
      (node (ref "U15") (pin "8") (pinfunction "BOUT2_8") (pintype "output"))
      (node (ref "X16") (pin "2") (pinfunction "S_2") (pintype "passive"))
    )
    (net (code "138") (name "Net-(U15-CP1)") (class "Default")
      (node (ref "C5") (pin "2") (pinfunction "2_2") (pintype "passive"))
      (node (ref "U15") (pin "1") (pinfunction "CP1_1") (pintype "bidirectional"))
    )
    (net (code "139") (name "Net-(U15-CP2)") (class "Default")
      (node (ref "C5") (pin "1") (pinfunction "1_1") (pintype "passive"))
      (node (ref "U15") (pin "2") (pinfunction "CP2_2") (pintype "bidirectional"))
    )
    (net (code "140") (name "Net-(U15-DECAY)") (class "Default")
      (node (ref "U15") (pin "19") (pinfunction "DECAY_19") (pintype "input"))
      (node (ref "U3") (pin "5") (pinfunction "QF_5") (pintype "output"))
    )
    (net (code "141") (name "Net-(U15-ENBL)") (class "Default")
      (node (ref "U15") (pin "21") (pinfunction "ENBL_21") (pintype "input"))
      (node (ref "U3") (pin "4") (pinfunction "QE_4") (pintype "output"))
    )
    (net (code "142") (name "Net-(U15-ISENA)") (class "Default")
      (node (ref "R6") (pin "2") (pinfunction "2_2") (pintype "passive"))
      (node (ref "U15") (pin "6") (pinfunction "ISENA_6") (pintype "output"))
    )
    (net (code "143") (name "Net-(U15-ISENB)") (class "Default")
      (node (ref "R5") (pin "2") (pinfunction "2_2") (pintype "passive"))
      (node (ref "U15") (pin "9") (pinfunction "ISENB_9") (pintype "output"))
    )
    (net (code "144") (name "Net-(U15-MODE0)") (class "Default")
      (node (ref "U15") (pin "24") (pinfunction "MODE0_24") (pintype "input"))
      (node (ref "U3") (pin "3") (pinfunction "QD_3") (pintype "output"))
    )
    (net (code "145") (name "Net-(U15-MODE1)") (class "Default")
      (node (ref "U15") (pin "25") (pinfunction "MODE1_25") (pintype "input"))
      (node (ref "U3") (pin "2") (pinfunction "QC_2") (pintype "output"))
    )
    (net (code "146") (name "Net-(U15-MODE2)") (class "Default")
      (node (ref "U15") (pin "26") (pinfunction "MODE2_26") (pintype "input"))
      (node (ref "U3") (pin "1") (pinfunction "QB_1") (pintype "output"))
    )
    (net (code "147") (name "Net-(U15-RESET)") (class "Default")
      (node (ref "U15") (pin "16") (pinfunction "RESET_16") (pintype "input"))
      (node (ref "U3") (pin "7") (pinfunction "QH_7") (pintype "output"))
    )
    (net (code "148") (name "Net-(U15-SLEEP)") (class "Default")
      (node (ref "U15") (pin "17") (pinfunction "SLEEP_17") (pintype "input"))
      (node (ref "U3") (pin "6") (pinfunction "QG_6") (pintype "output"))
    )
    (net (code "149") (name "Net-(U15-VCP)") (class "Default")
      (node (ref "C6") (pin "2") (pinfunction "2_2") (pintype "passive"))
      (node (ref "U15") (pin "3") (pinfunction "VCP_3") (pintype "bidirectional"))
    )
    (net (code "150") (name "Net-(U16-AOUT1)") (class "Default")
      (node (ref "U16") (pin "5") (pinfunction "AOUT1_5") (pintype "output"))
      (node (ref "X17") (pin "4") (pinfunction "S_4") (pintype "passive"))
    )
    (net (code "151") (name "Net-(U16-AOUT2)") (class "Default")
      (node (ref "U16") (pin "7") (pinfunction "AOUT2_7") (pintype "output"))
      (node (ref "X17") (pin "3") (pinfunction "S_3") (pintype "passive"))
    )
    (net (code "152") (name "Net-(U16-BOUT1)") (class "Default")
      (node (ref "U16") (pin "10") (pinfunction "BOUT1_10") (pintype "output"))
      (node (ref "X17") (pin "1") (pinfunction "S_1") (pintype "passive"))
    )
    (net (code "153") (name "Net-(U16-BOUT2)") (class "Default")
      (node (ref "U16") (pin "8") (pinfunction "BOUT2_8") (pintype "output"))
      (node (ref "X17") (pin "2") (pinfunction "S_2") (pintype "passive"))
    )
    (net (code "154") (name "Net-(U16-CP1)") (class "Default")
      (node (ref "C7") (pin "2") (pinfunction "2_2") (pintype "passive"))
      (node (ref "U16") (pin "1") (pinfunction "CP1_1") (pintype "bidirectional"))
    )
    (net (code "155") (name "Net-(U16-CP2)") (class "Default")
      (node (ref "C7") (pin "1") (pinfunction "1_1") (pintype "passive"))
      (node (ref "U16") (pin "2") (pinfunction "CP2_2") (pintype "bidirectional"))
    )
    (net (code "156") (name "Net-(U16-DECAY)") (class "Default")
      (node (ref "U16") (pin "19") (pinfunction "DECAY_19") (pintype "input"))
      (node (ref "U4") (pin "5") (pinfunction "QF_5") (pintype "output"))
    )
    (net (code "157") (name "Net-(U16-ENBL)") (class "Default")
      (node (ref "U16") (pin "21") (pinfunction "ENBL_21") (pintype "input"))
      (node (ref "U4") (pin "4") (pinfunction "QE_4") (pintype "output"))
    )
    (net (code "158") (name "Net-(U16-ISENA)") (class "Default")
      (node (ref "R8") (pin "2") (pinfunction "2_2") (pintype "passive"))
      (node (ref "U16") (pin "6") (pinfunction "ISENA_6") (pintype "output"))
    )
    (net (code "159") (name "Net-(U16-ISENB)") (class "Default")
      (node (ref "R7") (pin "2") (pinfunction "2_2") (pintype "passive"))
      (node (ref "U16") (pin "9") (pinfunction "ISENB_9") (pintype "output"))
    )
    (net (code "160") (name "Net-(U16-MODE0)") (class "Default")
      (node (ref "U16") (pin "24") (pinfunction "MODE0_24") (pintype "input"))
      (node (ref "U4") (pin "3") (pinfunction "QD_3") (pintype "output"))
    )
    (net (code "161") (name "Net-(U16-MODE1)") (class "Default")
      (node (ref "U16") (pin "25") (pinfunction "MODE1_25") (pintype "input"))
      (node (ref "U4") (pin "2") (pinfunction "QC_2") (pintype "output"))
    )
    (net (code "162") (name "Net-(U16-MODE2)") (class "Default")
      (node (ref "U16") (pin "26") (pinfunction "MODE2_26") (pintype "input"))
      (node (ref "U4") (pin "1") (pinfunction "QB_1") (pintype "output"))
    )
    (net (code "163") (name "Net-(U16-RESET)") (class "Default")
      (node (ref "U16") (pin "16") (pinfunction "RESET_16") (pintype "input"))
      (node (ref "U4") (pin "7") (pinfunction "QH_7") (pintype "output"))
    )
    (net (code "164") (name "Net-(U16-SLEEP)") (class "Default")
      (node (ref "U16") (pin "17") (pinfunction "SLEEP_17") (pintype "input"))
      (node (ref "U4") (pin "6") (pinfunction "QG_6") (pintype "output"))
    )
    (net (code "165") (name "Net-(U16-VCP)") (class "Default")
      (node (ref "C8") (pin "2") (pinfunction "2_2") (pintype "passive"))
      (node (ref "U16") (pin "3") (pinfunction "VCP_3") (pintype "bidirectional"))
    )
    (net (code "166") (name "Net-(U17-AOUT1)") (class "Default")
      (node (ref "U17") (pin "5") (pinfunction "AOUT1_5") (pintype "output"))
      (node (ref "X18") (pin "4") (pinfunction "S_4") (pintype "passive"))
    )
    (net (code "167") (name "Net-(U17-AOUT2)") (class "Default")
      (node (ref "U17") (pin "7") (pinfunction "AOUT2_7") (pintype "output"))
      (node (ref "X18") (pin "3") (pinfunction "S_3") (pintype "passive"))
    )
    (net (code "168") (name "Net-(U17-BOUT1)") (class "Default")
      (node (ref "U17") (pin "10") (pinfunction "BOUT1_10") (pintype "output"))
      (node (ref "X18") (pin "1") (pinfunction "S_1") (pintype "passive"))
    )
    (net (code "169") (name "Net-(U17-BOUT2)") (class "Default")
      (node (ref "U17") (pin "8") (pinfunction "BOUT2_8") (pintype "output"))
      (node (ref "X18") (pin "2") (pinfunction "S_2") (pintype "passive"))
    )
    (net (code "170") (name "Net-(U17-CP1)") (class "Default")
      (node (ref "C9") (pin "2") (pinfunction "2_2") (pintype "passive"))
      (node (ref "U17") (pin "1") (pinfunction "CP1_1") (pintype "bidirectional"))
    )
    (net (code "171") (name "Net-(U17-CP2)") (class "Default")
      (node (ref "C9") (pin "1") (pinfunction "1_1") (pintype "passive"))
      (node (ref "U17") (pin "2") (pinfunction "CP2_2") (pintype "bidirectional"))
    )
    (net (code "172") (name "Net-(U17-DECAY)") (class "Default")
      (node (ref "U17") (pin "19") (pinfunction "DECAY_19") (pintype "input"))
      (node (ref "U5") (pin "5") (pinfunction "QF_5") (pintype "output"))
    )
    (net (code "173") (name "Net-(U17-ENBL)") (class "Default")
      (node (ref "U17") (pin "21") (pinfunction "ENBL_21") (pintype "input"))
      (node (ref "U5") (pin "4") (pinfunction "QE_4") (pintype "output"))
    )
    (net (code "174") (name "Net-(U17-ISENA)") (class "Default")
      (node (ref "R10") (pin "2") (pinfunction "2_2") (pintype "passive"))
      (node (ref "U17") (pin "6") (pinfunction "ISENA_6") (pintype "output"))
    )
    (net (code "175") (name "Net-(U17-ISENB)") (class "Default")
      (node (ref "R9") (pin "2") (pinfunction "2_2") (pintype "passive"))
      (node (ref "U17") (pin "9") (pinfunction "ISENB_9") (pintype "output"))
    )
    (net (code "176") (name "Net-(U17-MODE0)") (class "Default")
      (node (ref "U17") (pin "24") (pinfunction "MODE0_24") (pintype "input"))
      (node (ref "U5") (pin "3") (pinfunction "QD_3") (pintype "output"))
    )
    (net (code "177") (name "Net-(U17-MODE1)") (class "Default")
      (node (ref "U17") (pin "25") (pinfunction "MODE1_25") (pintype "input"))
      (node (ref "U5") (pin "2") (pinfunction "QC_2") (pintype "output"))
    )
    (net (code "178") (name "Net-(U17-MODE2)") (class "Default")
      (node (ref "U17") (pin "26") (pinfunction "MODE2_26") (pintype "input"))
      (node (ref "U5") (pin "1") (pinfunction "QB_1") (pintype "output"))
    )
    (net (code "179") (name "Net-(U17-RESET)") (class "Default")
      (node (ref "U17") (pin "16") (pinfunction "RESET_16") (pintype "input"))
      (node (ref "U5") (pin "7") (pinfunction "QH_7") (pintype "output"))
    )
    (net (code "180") (name "Net-(U17-SLEEP)") (class "Default")
      (node (ref "U17") (pin "17") (pinfunction "SLEEP_17") (pintype "input"))
      (node (ref "U5") (pin "6") (pinfunction "QG_6") (pintype "output"))
    )
    (net (code "181") (name "Net-(U17-VCP)") (class "Default")
      (node (ref "C10") (pin "2") (pinfunction "2_2") (pintype "passive"))
      (node (ref "U17") (pin "3") (pinfunction "VCP_3") (pintype "bidirectional"))
    )
    (net (code "182") (name "Net-(U18-A0)") (class "Default")
      (node (ref "R24") (pin "1") (pinfunction "1_1") (pintype "passive"))
      (node (ref "S2") (pin "3") (pinfunction "3_3") (pintype "passive"))
      (node (ref "U18") (pin "1") (pinfunction "A0_1") (pintype "input"))
    )
    (net (code "183") (name "Net-(U18-A1)") (class "Default")
      (node (ref "R23") (pin "1") (pinfunction "1_1") (pintype "passive"))
      (node (ref "S2") (pin "4") (pinfunction "4_4") (pintype "passive"))
      (node (ref "U18") (pin "2") (pinfunction "A1_2") (pintype "input"))
    )
    (net (code "184") (name "Net-(U18-A2)") (class "Default")
      (node (ref "R22") (pin "1") (pinfunction "1_1") (pintype "passive"))
      (node (ref "U18") (pin "3") (pinfunction "A2_3") (pintype "input"))
    )
    (net (code "185") (name "Net-(X3B-1)") (class "Default")
      (node (ref "C59") (pin "1") (pinfunction "1_1") (pintype "passive"))
      (node (ref "D1") (pin "A") (pinfunction "A_A") (pintype "passive"))
      (node (ref "LED3") (pin "C") (pinfunction "C_C") (pintype "passive"))
      (node (ref "Q3") (pin "5") (pinfunction "D_5") (pintype "passive"))
      (node (ref "Q3") (pin "6") (pinfunction "D_6") (pintype "passive"))
      (node (ref "Q3") (pin "7") (pinfunction "D_7") (pintype "passive"))
      (node (ref "Q3") (pin "8") (pinfunction "D_8") (pintype "passive"))
      (node (ref "Q3") (pin "TH") (pinfunction "D_TH") (pintype "passive"))
      (node (ref "R55") (pin "1") (pinfunction "1_1") (pintype "passive"))
      (node (ref "X3") (pin "2") (pinfunction "1_2") (pintype "passive"))
    )
    (net (code "186") (name "Net-(X4B-S)") (class "Default")
      (node (ref "LED5") (pin "C") (pinfunction "C_C") (pintype "passive"))
      (node (ref "Q4") (pin "2") (pinfunction "D_2") (pintype "passive"))
      (node (ref "Q4") (pin "4") (pinfunction "D_4") (pintype "passive"))
      (node (ref "X4") (pin "2") (pinfunction "S_2") (pintype "passive"))
    )
    (net (code "187") (name "Net-(X5B-S)") (class "Default")
      (node (ref "LED6") (pin "C") (pinfunction "C_C") (pintype "passive"))
      (node (ref "Q5") (pin "2") (pinfunction "D_2") (pintype "passive"))
      (node (ref "Q5") (pin "4") (pinfunction "D_4") (pintype "passive"))
      (node (ref "X5") (pin "2") (pinfunction "S_2") (pintype "passive"))
    )
    (net (code "188") (name "Net-(X6B-S)") (class "Default")
      (node (ref "LED7") (pin "C") (pinfunction "C_C") (pintype "passive"))
      (node (ref "Q6") (pin "2") (pinfunction "D_2") (pintype "passive"))
      (node (ref "Q6") (pin "4") (pinfunction "D_4") (pintype "passive"))
      (node (ref "X6") (pin "2") (pinfunction "S_2") (pintype "passive"))
    )
    (net (code "189") (name "Net-(X7A-S)") (class "Default")
      (node (ref "C16") (pin "1") (pinfunction "1_1") (pintype "passive"))
      (node (ref "R18") (pin "1") (pinfunction "1_1") (pintype "passive"))
      (node (ref "R40") (pin "1") (pinfunction "1_1") (pintype "passive"))
      (node (ref "X7") (pin "1") (pinfunction "S_1") (pintype "passive"))
    )
    (net (code "190") (name "Net-(X8A-S)") (class "Default")
      (node (ref "C15") (pin "1") (pinfunction "1_1") (pintype "passive"))
      (node (ref "R17") (pin "1") (pinfunction "1_1") (pintype "passive"))
      (node (ref "R39") (pin "1") (pinfunction "1_1") (pintype "passive"))
      (node (ref "X8") (pin "1") (pinfunction "S_1") (pintype "passive"))
    )
    (net (code "191") (name "Net-(X9A-S)") (class "Default")
      (node (ref "C14") (pin "1") (pinfunction "1_1") (pintype "passive"))
      (node (ref "R13") (pin "1") (pinfunction "1_1") (pintype "passive"))
      (node (ref "R38") (pin "1") (pinfunction "1_1") (pintype "passive"))
      (node (ref "X9") (pin "1") (pinfunction "S_1") (pintype "passive"))
    )
    (net (code "192") (name "Net-(X20C-1)") (class "Default")
      (node (ref "C58") (pin "1") (pinfunction "1_1") (pintype "passive"))
      (node (ref "D2") (pin "A") (pinfunction "A_A") (pintype "passive"))
      (node (ref "LED2") (pin "C") (pinfunction "C_C") (pintype "passive"))
      (node (ref "Q1") (pin "5") (pinfunction "D_5") (pintype "passive"))
      (node (ref "Q1") (pin "6") (pinfunction "D_6") (pintype "passive"))
      (node (ref "Q1") (pin "7") (pinfunction "D_7") (pintype "passive"))
      (node (ref "Q1") (pin "8") (pinfunction "D_8") (pintype "passive"))
      (node (ref "Q1") (pin "TH") (pinfunction "D_TH") (pintype "passive"))
      (node (ref "R56") (pin "1") (pinfunction "1_1") (pintype "passive"))
      (node (ref "X20") (pin "3") (pinfunction "1_3") (pintype "passive"))
      (node (ref "X20") (pin "4") (pinfunction "1_4") (pintype "passive"))
    )
    (net (code "193") (name "Net-(X21B-1)") (class "Default")
      (node (ref "C57") (pin "1") (pinfunction "1_1") (pintype "passive"))
      (node (ref "D3") (pin "A") (pinfunction "A_A") (pintype "passive"))
      (node (ref "LED1") (pin "C") (pinfunction "C_C") (pintype "passive"))
      (node (ref "Q2") (pin "5") (pinfunction "D_5") (pintype "passive"))
      (node (ref "Q2") (pin "6") (pinfunction "D_6") (pintype "passive"))
      (node (ref "Q2") (pin "7") (pinfunction "D_7") (pintype "passive"))
      (node (ref "Q2") (pin "8") (pinfunction "D_8") (pintype "passive"))
      (node (ref "Q2") (pin "TH") (pinfunction "D_TH") (pintype "passive"))
      (node (ref "R57") (pin "1") (pinfunction "1_1") (pintype "passive"))
      (node (ref "X21") (pin "2") (pinfunction "1_2") (pintype "passive"))
    )
    (net (code "194") (name "unconnected-(P8-Pad3)") (class "Default")
      (node (ref "P8") (pin "3") (pinfunction "3_3") (pintype "passive"))
    )
    (net (code "195") (name "unconnected-(P8-Pad4)") (class "Default")
      (node (ref "P8") (pin "4") (pinfunction "4_4") (pintype "passive"))
    )
    (net (code "196") (name "unconnected-(P8-Pad5)") (class "Default")
      (node (ref "P8") (pin "5") (pinfunction "5_5") (pintype "passive"))
    )
    (net (code "197") (name "unconnected-(P8-Pad6)") (class "Default")
      (node (ref "P8") (pin "6") (pinfunction "6_6") (pintype "passive"))
    )
    (net (code "198") (name "unconnected-(P8-Pad7)") (class "Default")
      (node (ref "P8") (pin "7") (pinfunction "7_7") (pintype "passive"))
    )
    (net (code "199") (name "unconnected-(P8-Pad20)") (class "Default")
      (node (ref "P8") (pin "20") (pinfunction "20_20") (pintype "passive"))
    )
    (net (code "200") (name "unconnected-(P8-Pad21)") (class "Default")
      (node (ref "P8") (pin "21") (pinfunction "21_21") (pintype "passive"))
    )
    (net (code "201") (name "unconnected-(P8-Pad22)") (class "Default")
      (node (ref "P8") (pin "22") (pinfunction "22_22") (pintype "passive"))
    )
    (net (code "202") (name "unconnected-(P8-Pad23)") (class "Default")
      (node (ref "P8") (pin "23") (pinfunction "23_23") (pintype "passive"))
    )
    (net (code "203") (name "unconnected-(P8-Pad24)") (class "Default")
      (node (ref "P8") (pin "24") (pinfunction "24_24") (pintype "passive"))
    )
    (net (code "204") (name "unconnected-(P8-Pad25)") (class "Default")
      (node (ref "P8") (pin "25") (pinfunction "25_25") (pintype "passive"))
    )
    (net (code "205") (name "unconnected-(P8-Pad27)") (class "Default")
      (node (ref "P8") (pin "27") (pinfunction "27_27") (pintype "passive"))
    )
    (net (code "206") (name "unconnected-(P8-Pad28)") (class "Default")
      (node (ref "P8") (pin "28") (pinfunction "28_28") (pintype "passive"))
    )
    (net (code "207") (name "unconnected-(P8-Pad29)") (class "Default")
      (node (ref "P8") (pin "29") (pinfunction "29_29") (pintype "passive"))
    )
    (net (code "208") (name "unconnected-(P8-Pad30)") (class "Default")
      (node (ref "P8") (pin "30") (pinfunction "30_30") (pintype "passive"))
    )
    (net (code "209") (name "unconnected-(P8-Pad31)") (class "Default")
      (node (ref "P8") (pin "31") (pinfunction "31_31") (pintype "passive"))
    )
    (net (code "210") (name "unconnected-(P8-Pad32)") (class "Default")
      (node (ref "P8") (pin "32") (pinfunction "32_32") (pintype "passive"))
    )
    (net (code "211") (name "unconnected-(P8-Pad33)") (class "Default")
      (node (ref "P8") (pin "33") (pinfunction "33_33") (pintype "passive"))
    )
    (net (code "212") (name "unconnected-(P8-Pad34)") (class "Default")
      (node (ref "P8") (pin "34") (pinfunction "34_34") (pintype "passive"))
    )
    (net (code "213") (name "unconnected-(P8-Pad35)") (class "Default")
      (node (ref "P8") (pin "35") (pinfunction "35_35") (pintype "passive"))
    )
    (net (code "214") (name "unconnected-(P8-Pad36)") (class "Default")
      (node (ref "P8") (pin "36") (pinfunction "36_36") (pintype "passive"))
    )
    (net (code "215") (name "unconnected-(P8-Pad37)") (class "Default")
      (node (ref "P8") (pin "37") (pinfunction "37_37") (pintype "passive"))
    )
    (net (code "216") (name "unconnected-(P8-Pad38)") (class "Default")
      (node (ref "P8") (pin "38") (pinfunction "38_38") (pintype "passive"))
    )
    (net (code "217") (name "unconnected-(P8-Pad39)") (class "Default")
      (node (ref "P8") (pin "39") (pinfunction "39_39") (pintype "passive"))
    )
    (net (code "218") (name "unconnected-(P8-Pad40)") (class "Default")
      (node (ref "P8") (pin "40") (pinfunction "40_40") (pintype "passive"))
    )
    (net (code "219") (name "unconnected-(P8-Pad41)") (class "Default")
      (node (ref "P8") (pin "41") (pinfunction "41_41") (pintype "passive"))
    )
    (net (code "220") (name "unconnected-(P8-Pad42)") (class "Default")
      (node (ref "P8") (pin "42") (pinfunction "42_42") (pintype "passive"))
    )
    (net (code "221") (name "unconnected-(P8-Pad43)") (class "Default")
      (node (ref "P8") (pin "43") (pinfunction "43_43") (pintype "passive"))
    )
    (net (code "222") (name "unconnected-(P8-Pad44)") (class "Default")
      (node (ref "P8") (pin "44") (pinfunction "44_44") (pintype "passive"))
    )
    (net (code "223") (name "unconnected-(P8-Pad45)") (class "Default")
      (node (ref "P8") (pin "45") (pinfunction "45_45") (pintype "passive"))
    )
    (net (code "224") (name "unconnected-(P8-Pad46)") (class "Default")
      (node (ref "P8") (pin "46") (pinfunction "46_46") (pintype "passive"))
    )
    (net (code "225") (name "unconnected-(P9-Pad7)") (class "Default")
      (node (ref "P9") (pin "7") (pinfunction "7_7") (pintype "passive"))
    )
    (net (code "226") (name "unconnected-(P9-Pad9)") (class "Default")
      (node (ref "P9") (pin "9") (pinfunction "9_9") (pintype "passive"))
    )
    (net (code "227") (name "unconnected-(P9-Pad10)") (class "Default")
      (node (ref "P9") (pin "10") (pinfunction "10_10") (pintype "passive"))
    )
    (net (code "228") (name "unconnected-(P9-Pad14)") (class "Default")
      (node (ref "P9") (pin "14") (pinfunction "14_14") (pintype "passive"))
    )
    (net (code "229") (name "unconnected-(P9-Pad15)") (class "Default")
      (node (ref "P9") (pin "15") (pinfunction "15_15") (pintype "passive"))
    )
    (net (code "230") (name "unconnected-(P9-Pad17)") (class "Default")
      (node (ref "P9") (pin "17") (pinfunction "17_17") (pintype "passive"))
    )
    (net (code "231") (name "unconnected-(P9-Pad21)") (class "Default")
      (node (ref "P9") (pin "21") (pinfunction "21_21") (pintype "passive"))
    )
    (net (code "232") (name "unconnected-(P9-Pad26)") (class "Default")
      (node (ref "P9") (pin "26") (pinfunction "26_26") (pintype "passive"))
    )
    (net (code "233") (name "unconnected-(P9-Pad27)") (class "Default")
      (node (ref "P9") (pin "27") (pinfunction "27_27") (pintype "passive"))
    )
    (net (code "234") (name "unconnected-(P9-Pad37)") (class "Default")
      (node (ref "P9") (pin "37") (pinfunction "37_37") (pintype "passive"))
    )
    (net (code "235") (name "unconnected-(P9-Pad38)") (class "Default")
      (node (ref "P9") (pin "38") (pinfunction "38_38") (pintype "passive"))
    )
    (net (code "236") (name "unconnected-(P9-Pad39)") (class "Default")
      (node (ref "P9") (pin "39") (pinfunction "39_39") (pintype "passive"))
    )
    (net (code "237") (name "unconnected-(P9-Pad40)") (class "Default")
      (node (ref "P9") (pin "40") (pinfunction "40_40") (pintype "passive"))
    )
    (net (code "238") (name "unconnected-(P9-Pad41)") (class "Default")
      (node (ref "P9") (pin "41") (pinfunction "41_41") (pintype "passive"))
    )
    (net (code "239") (name "unconnected-(U1-QA-Pad15)") (class "Default")
      (node (ref "U1") (pin "15") (pinfunction "QA_15") (pintype "output"))
    )
    (net (code "240") (name "unconnected-(U2-QA-Pad15)") (class "Default")
      (node (ref "U2") (pin "15") (pinfunction "QA_15") (pintype "output"))
    )
    (net (code "241") (name "unconnected-(U3-QA-Pad15)") (class "Default")
      (node (ref "U3") (pin "15") (pinfunction "QA_15") (pintype "output"))
    )
    (net (code "242") (name "unconnected-(U4-QA-Pad15)") (class "Default")
      (node (ref "U4") (pin "15") (pinfunction "QA_15") (pintype "output"))
    )
    (net (code "243") (name "unconnected-(U5-QA-Pad15)") (class "Default")
      (node (ref "U5") (pin "15") (pinfunction "QA_15") (pintype "output"))
    )
    (net (code "244") (name "unconnected-(U6-EN-Pad9)") (class "Default")
      (node (ref "U6") (pin "9") (pinfunction "EN_9") (pintype "input"))
    )
    (net (code "245") (name "unconnected-(U10-EN-Pad9)") (class "Default")
      (node (ref "U10") (pin "9") (pinfunction "EN_9") (pintype "input"))
    )
    (net (code "246") (name "unconnected-(U11-EXTCLK-Pad25)") (class "Default")
      (node (ref "U11") (pin "25") (pinfunction "EXTCLK_25") (pintype "input"))
    )
    (net (code "247") (name "unconnected-(U11-LED0-Pad6)") (class "Default")
      (node (ref "U11") (pin "6") (pinfunction "LED0_6") (pintype "output"))
    )
    (net (code "248") (name "unconnected-(U11-LED1-Pad7)") (class "Default")
      (node (ref "U11") (pin "7") (pinfunction "LED1_7") (pintype "output"))
    )
    (net (code "249") (name "unconnected-(U11-LED2-Pad8)") (class "Default")
      (node (ref "U11") (pin "8") (pinfunction "LED2_8") (pintype "output"))
    )
    (net (code "250") (name "unconnected-(U11-LED6-Pad12)") (class "Default")
      (node (ref "U11") (pin "12") (pinfunction "LED6_12") (pintype "output"))
    )
    (net (code "251") (name "unconnected-(U13-HOME-Pad27)") (class "Default")
      (node (ref "U13") (pin "27") (pinfunction "HOME_27") (pintype "output"))
    )
    (net (code "252") (name "unconnected-(U13-V3P3OUT-Pad15)") (class "Default")
      (node (ref "U13") (pin "15") (pinfunction "V3P3OUT_15") (pintype "output"))
    )
    (net (code "253") (name "unconnected-(U14-HOME-Pad27)") (class "Default")
      (node (ref "U14") (pin "27") (pinfunction "HOME_27") (pintype "output"))
    )
    (net (code "254") (name "unconnected-(U14-V3P3OUT-Pad15)") (class "Default")
      (node (ref "U14") (pin "15") (pinfunction "V3P3OUT_15") (pintype "output"))
    )
    (net (code "255") (name "unconnected-(U15-HOME-Pad27)") (class "Default")
      (node (ref "U15") (pin "27") (pinfunction "HOME_27") (pintype "output"))
    )
    (net (code "256") (name "unconnected-(U15-V3P3OUT-Pad15)") (class "Default")
      (node (ref "U15") (pin "15") (pinfunction "V3P3OUT_15") (pintype "output"))
    )
    (net (code "257") (name "unconnected-(U16-HOME-Pad27)") (class "Default")
      (node (ref "U16") (pin "27") (pinfunction "HOME_27") (pintype "output"))
    )
    (net (code "258") (name "unconnected-(U16-V3P3OUT-Pad15)") (class "Default")
      (node (ref "U16") (pin "15") (pinfunction "V3P3OUT_15") (pintype "output"))
    )
    (net (code "259") (name "unconnected-(U17-HOME-Pad27)") (class "Default")
      (node (ref "U17") (pin "27") (pinfunction "HOME_27") (pintype "output"))
    )
    (net (code "260") (name "unconnected-(U17-V3P3OUT-Pad15)") (class "Default")
      (node (ref "U17") (pin "15") (pinfunction "V3P3OUT_15") (pintype "output"))
    )
    (net (code "261") (name "unconnected-(U18-~{WC}-Pad7)") (class "Default")
      (node (ref "U18") (pin "7") (pinfunction "~{WC}_7") (pintype "no_connect"))
    )
  )
)
